# Adapters.net
KiCad netlist of a schematic drawn in Altium Designer
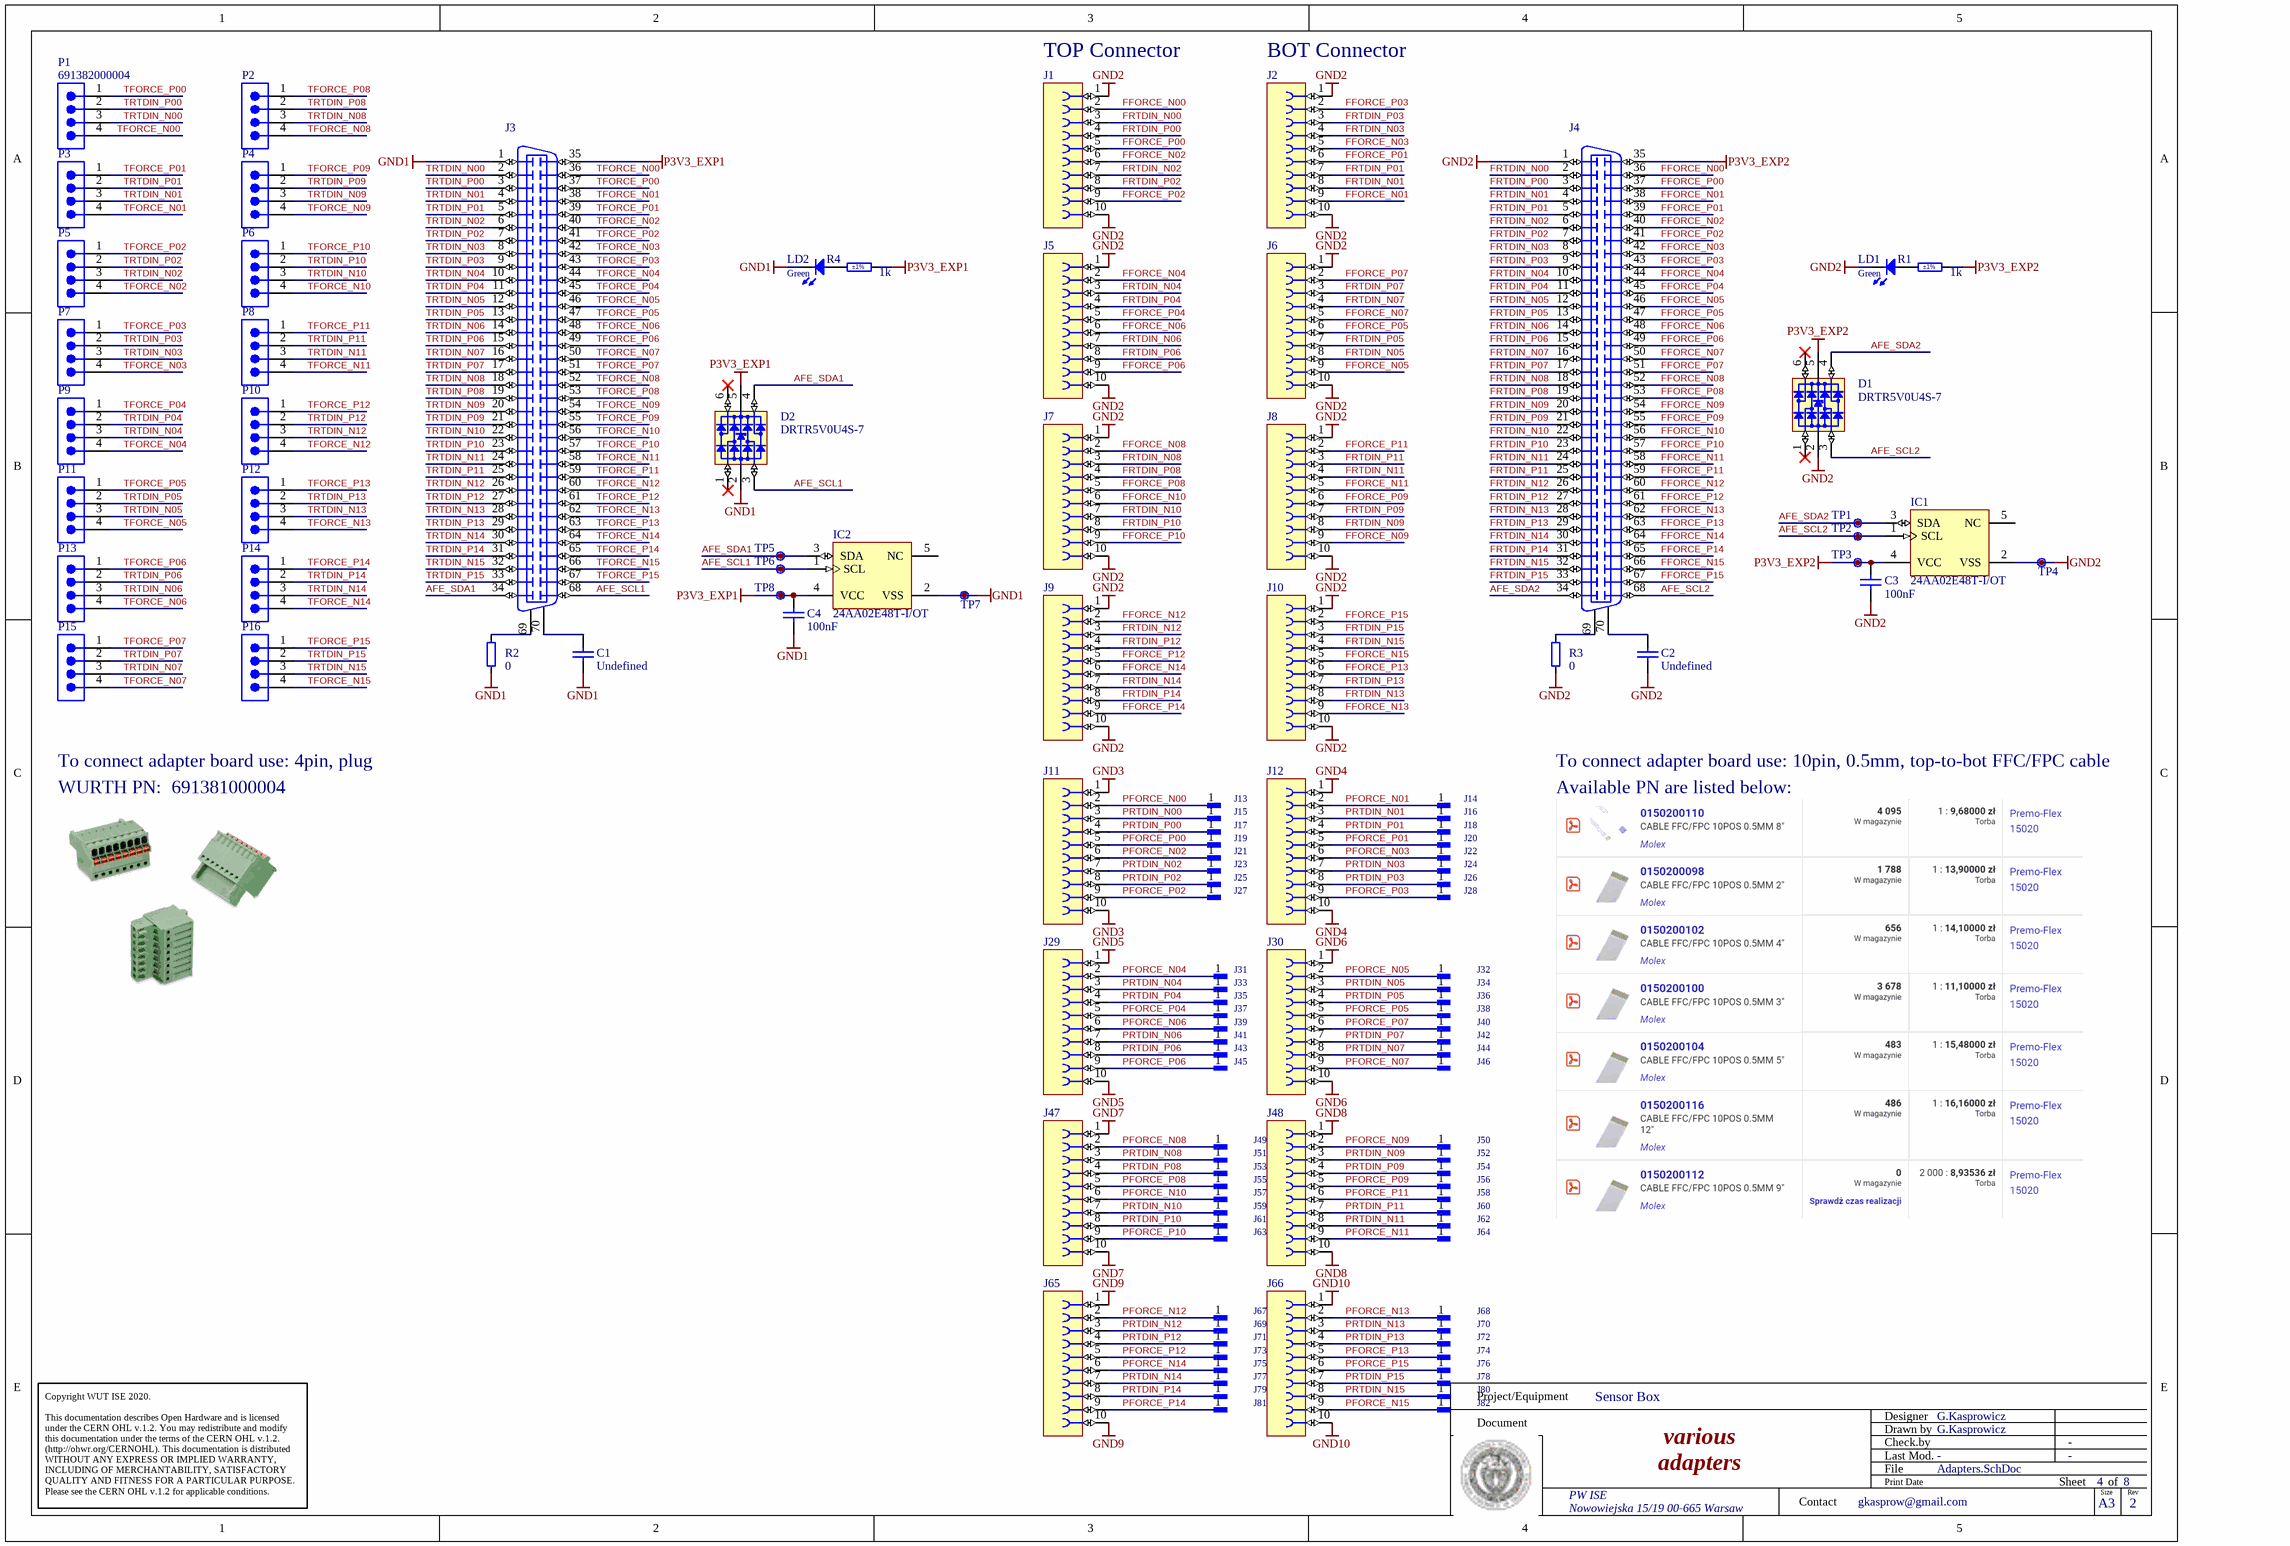
[diagram p0: Adapters.SchDoc]

(export (version "E")
  (design (tool "Eeschema 10.0.6"))
  (components
    (comp (ref "C1")
      (value "Undefined")
      (footprint "CAPC2012X135N")
      (description "Non-polarised capacitor")
      (fields (field (name "PART NUMBER") "CC0805_NO-VALUE") (field (name "AUTHOR") "CERN DEM JLC"))
      (libsource (lib "Capacitors") (part "Capacitor - non polarized"))
    )
    (comp (ref "C2")
      (value "Undefined")
      (footprint "CAPC2012X135N")
      (description "Non-polarised capacitor")
      (fields (field (name "PART NUMBER") "CC0805_NO-VALUE") (field (name "AUTHOR") "CERN DEM JLC"))
      (libsource (lib "Capacitors") (part "Capacitor - non polarized"))
    )
    (comp (ref "C3")
      (value "100nF")
      (footprint "CAPC1608X87N")
      (description "Non-polarised capacitor")
      (fields
        (field (name "PART NUMBER") "CC0603_100NF_50V_10%_X7R")
        (field (name "VOLTAGE") "50V")
        (field (name "AUTHOR") "CERN DEM JLC")
      )
      (libsource (lib "Capacitors") (part "Capacitor - non polarized"))
    )
    (comp (ref "C4")
      (value "100nF")
      (footprint "CAPC1608X87N")
      (description "Non-polarised capacitor")
      (fields
        (field (name "PART NUMBER") "CC0603_100NF_50V_10%_X7R")
        (field (name "VOLTAGE") "50V")
        (field (name "AUTHOR") "CERN DEM JLC")
      )
      (libsource (lib "Capacitors") (part "Capacitor - non polarized"))
    )
    (comp (ref "D1")
      (value "DRTR5V0U4S-7")
      (footprint "SOT65P210X110-6N")
      (description "Integrated Quad Ultra-Low Capacitance ESD Protection")
      (fields (field (name "MANUFACTURER") "DIODES") (field (name "AUTHOR") "GK"))
      (libsource (lib "Diodes") (part "D_TVS_DRTR5V0U4S-7"))
    )
    (comp (ref "D2")
      (value "DRTR5V0U4S-7")
      (footprint "SOT65P210X110-6N")
      (description "Integrated Quad Ultra-Low Capacitance ESD Protection")
      (fields (field (name "MANUFACTURER") "DIODES") (field (name "AUTHOR") "GK"))
      (libsource (lib "Diodes") (part "D_TVS_DRTR5V0U4S-7"))
    )
    (comp (ref "IC1")
      (value "24AA02E48T-I/OT")
      (footprint "SOT95P280X145-5N")
      (description "1.7V-5.5V, 2K I2C Serial EEPROM With EUI-48 Node Identity")
      (fields (field (name "MANUFACTURER") "MICROCHIP TECHNOLOGY") (field (name "AUTHOR") "CERN DEM MR"))
      (libsource (lib "ICs And Semiconductors") (part "24AA02E48T-I/OT"))
    )
    (comp (ref "IC2")
      (value "24AA02E48T-I/OT")
      (footprint "SOT95P280X145-5N")
      (description "1.7V-5.5V, 2K I2C Serial EEPROM With EUI-48 Node Identity")
      (fields (field (name "MANUFACTURER") "MICROCHIP TECHNOLOGY") (field (name "AUTHOR") "CERN DEM MR"))
      (libsource (lib "ICs And Semiconductors") (part "24AA02E48T-I/OT"))
    )
    (comp (ref "J1")
      (value "FFC/FPC")
      (footprint "MOLEX_52745-1097")
      (description "Connector 10 Female")
      (fields
        (field (name "PART NUMBER") "MOLEX_52745-1097")
        (field (name "MANUFACTURER") "MOLEX")
        (field (name "AUTHOR") "CERN DEM JLC")
      )
      (libsource (lib "Connectors") (part "Connector 10 Female"))
    )
    (comp (ref "J2")
      (value "FFC/FPC")
      (footprint "MOLEX_52745-1097")
      (description "Connector 10 Female")
      (fields
        (field (name "PART NUMBER") "MOLEX_52745-1097")
        (field (name "MANUFACTURER") "MOLEX")
        (field (name "AUTHOR") "CERN DEM JLC")
      )
      (libsource (lib "Connectors") (part "Connector 10 Female"))
    )
    (comp (ref "J3")
      (value "DNP")
      (footprint "MOLEX_71430-0013")
      (description "Very High Density Cable Interconnect (VHDCI ) 68 Female")
      (fields
        (field (name "PART NUMBER") "MOLEX_71430-0013")
        (field (name "MANUFACTURER") "MOLEX")
        (field (name "AUTHOR") "CERN DEM JLC")
      )
      (libsource (lib "DIOT_temperature_logger") (part "MOLEX_71430-0013"))
    )
    (comp (ref "J4")
      (value "DNP")
      (footprint "MOLEX_71430-0013")
      (description "Very High Density Cable Interconnect (VHDCI ) 68 Female")
      (fields
        (field (name "PART NUMBER") "MOLEX_71430-0013")
        (field (name "MANUFACTURER") "MOLEX")
        (field (name "AUTHOR") "CERN DEM JLC")
      )
      (libsource (lib "DIOT_temperature_logger") (part "MOLEX_71430-0013"))
    )
    (comp (ref "J5")
      (value "FFC/FPC")
      (footprint "MOLEX_52745-1097")
      (description "Connector 10 Female")
      (fields
        (field (name "PART NUMBER") "MOLEX_52745-1097")
        (field (name "MANUFACTURER") "MOLEX")
        (field (name "AUTHOR") "CERN DEM JLC")
      )
      (libsource (lib "Connectors") (part "Connector 10 Female"))
    )
    (comp (ref "J6")
      (value "FFC/FPC")
      (footprint "MOLEX_52745-1097")
      (description "Connector 10 Female")
      (fields
        (field (name "PART NUMBER") "MOLEX_52745-1097")
        (field (name "MANUFACTURER") "MOLEX")
        (field (name "AUTHOR") "CERN DEM JLC")
      )
      (libsource (lib "Connectors") (part "Connector 10 Female"))
    )
    (comp (ref "J7")
      (value "FFC/FPC")
      (footprint "MOLEX_52745-1097")
      (description "Connector 10 Female")
      (fields
        (field (name "PART NUMBER") "MOLEX_52745-1097")
        (field (name "MANUFACTURER") "MOLEX")
        (field (name "AUTHOR") "CERN DEM JLC")
      )
      (libsource (lib "Connectors") (part "Connector 10 Female"))
    )
    (comp (ref "J8")
      (value "FFC/FPC")
      (footprint "MOLEX_52745-1097")
      (description "Connector 10 Female")
      (fields
        (field (name "PART NUMBER") "MOLEX_52745-1097")
        (field (name "MANUFACTURER") "MOLEX")
        (field (name "AUTHOR") "CERN DEM JLC")
      )
      (libsource (lib "Connectors") (part "Connector 10 Female"))
    )
    (comp (ref "J9")
      (value "FFC/FPC")
      (footprint "MOLEX_52745-1097")
      (description "Connector 10 Female")
      (fields
        (field (name "PART NUMBER") "MOLEX_52745-1097")
        (field (name "MANUFACTURER") "MOLEX")
        (field (name "AUTHOR") "CERN DEM JLC")
      )
      (libsource (lib "Connectors") (part "Connector 10 Female"))
    )
    (comp (ref "J10")
      (value "FFC/FPC")
      (footprint "MOLEX_52745-1097")
      (description "Connector 10 Female")
      (fields
        (field (name "PART NUMBER") "MOLEX_52745-1097")
        (field (name "MANUFACTURER") "MOLEX")
        (field (name "AUTHOR") "CERN DEM JLC")
      )
      (libsource (lib "Connectors") (part "Connector 10 Female"))
    )
    (comp (ref "J11")
      (value "FFC/FPC")
      (footprint "MOLEX_52745-1097")
      (description "Connector 10 Female")
      (fields
        (field (name "PART NUMBER") "MOLEX_52745-1097")
        (field (name "MANUFACTURER") "MOLEX")
        (field (name "AUTHOR") "CERN DEM JLC")
      )
      (libsource (lib "Connectors") (part "Connector 10 Female"))
    )
    (comp (ref "J12")
      (value "FFC/FPC")
      (footprint "MOLEX_52745-1097")
      (description "Connector 10 Female")
      (fields
        (field (name "PART NUMBER") "MOLEX_52745-1097")
        (field (name "MANUFACTURER") "MOLEX")
        (field (name "AUTHOR") "CERN DEM JLC")
      )
      (libsource (lib "Connectors") (part "Connector 10 Female"))
    )
    (comp (ref "J13")
      (value "SMD Pad")
      (footprint "R350X200")
      (description "Pad")
      (fields (field (name "PART NUMBER") "SMD_PAD_3.5X2MM") (field (name "AUTHOR") "CERN DEM JLC"))
      (libsource (lib "Eletro-mechanical") (part "Single SMD Pad"))
    )
    (comp (ref "J14")
      (value "SMD Pad")
      (footprint "R350X200")
      (description "Pad")
      (fields (field (name "PART NUMBER") "SMD_PAD_3.5X2MM") (field (name "AUTHOR") "CERN DEM JLC"))
      (libsource (lib "Eletro-mechanical") (part "Single SMD Pad"))
    )
    (comp (ref "J15")
      (value "SMD Pad")
      (footprint "R350X200")
      (description "Pad")
      (fields (field (name "PART NUMBER") "SMD_PAD_3.5X2MM") (field (name "AUTHOR") "CERN DEM JLC"))
      (libsource (lib "Eletro-mechanical") (part "Single SMD Pad"))
    )
    (comp (ref "J16")
      (value "SMD Pad")
      (footprint "R350X200")
      (description "Pad")
      (fields (field (name "PART NUMBER") "SMD_PAD_3.5X2MM") (field (name "AUTHOR") "CERN DEM JLC"))
      (libsource (lib "Eletro-mechanical") (part "Single SMD Pad"))
    )
    (comp (ref "J17")
      (value "SMD Pad")
      (footprint "R350X200")
      (description "Pad")
      (fields (field (name "PART NUMBER") "SMD_PAD_3.5X2MM") (field (name "AUTHOR") "CERN DEM JLC"))
      (libsource (lib "Eletro-mechanical") (part "Single SMD Pad"))
    )
    (comp (ref "J18")
      (value "SMD Pad")
      (footprint "R350X200")
      (description "Pad")
      (fields (field (name "PART NUMBER") "SMD_PAD_3.5X2MM") (field (name "AUTHOR") "CERN DEM JLC"))
      (libsource (lib "Eletro-mechanical") (part "Single SMD Pad"))
    )
    (comp (ref "J19")
      (value "SMD Pad")
      (footprint "R350X200")
      (description "Pad")
      (fields (field (name "PART NUMBER") "SMD_PAD_3.5X2MM") (field (name "AUTHOR") "CERN DEM JLC"))
      (libsource (lib "Eletro-mechanical") (part "Single SMD Pad"))
    )
    (comp (ref "J20")
      (value "SMD Pad")
      (footprint "R350X200")
      (description "Pad")
      (fields (field (name "PART NUMBER") "SMD_PAD_3.5X2MM") (field (name "AUTHOR") "CERN DEM JLC"))
      (libsource (lib "Eletro-mechanical") (part "Single SMD Pad"))
    )
    (comp (ref "J21")
      (value "SMD Pad")
      (footprint "R350X200")
      (description "Pad")
      (fields (field (name "PART NUMBER") "SMD_PAD_3.5X2MM") (field (name "AUTHOR") "CERN DEM JLC"))
      (libsource (lib "Eletro-mechanical") (part "Single SMD Pad"))
    )
    (comp (ref "J22")
      (value "SMD Pad")
      (footprint "R350X200")
      (description "Pad")
      (fields (field (name "PART NUMBER") "SMD_PAD_3.5X2MM") (field (name "AUTHOR") "CERN DEM JLC"))
      (libsource (lib "Eletro-mechanical") (part "Single SMD Pad"))
    )
    (comp (ref "J23")
      (value "SMD Pad")
      (footprint "R350X200")
      (description "Pad")
      (fields (field (name "PART NUMBER") "SMD_PAD_3.5X2MM") (field (name "AUTHOR") "CERN DEM JLC"))
      (libsource (lib "Eletro-mechanical") (part "Single SMD Pad"))
    )
    (comp (ref "J24")
      (value "SMD Pad")
      (footprint "R350X200")
      (description "Pad")
      (fields (field (name "PART NUMBER") "SMD_PAD_3.5X2MM") (field (name "AUTHOR") "CERN DEM JLC"))
      (libsource (lib "Eletro-mechanical") (part "Single SMD Pad"))
    )
    (comp (ref "J25")
      (value "SMD Pad")
      (footprint "R350X200")
      (description "Pad")
      (fields (field (name "PART NUMBER") "SMD_PAD_3.5X2MM") (field (name "AUTHOR") "CERN DEM JLC"))
      (libsource (lib "Eletro-mechanical") (part "Single SMD Pad"))
    )
    (comp (ref "J26")
      (value "SMD Pad")
      (footprint "R350X200")
      (description "Pad")
      (fields (field (name "PART NUMBER") "SMD_PAD_3.5X2MM") (field (name "AUTHOR") "CERN DEM JLC"))
      (libsource (lib "Eletro-mechanical") (part "Single SMD Pad"))
    )
    (comp (ref "J27")
      (value "SMD Pad")
      (footprint "R350X200")
      (description "Pad")
      (fields (field (name "PART NUMBER") "SMD_PAD_3.5X2MM") (field (name "AUTHOR") "CERN DEM JLC"))
      (libsource (lib "Eletro-mechanical") (part "Single SMD Pad"))
    )
    (comp (ref "J28")
      (value "SMD Pad")
      (footprint "R350X200")
      (description "Pad")
      (fields (field (name "PART NUMBER") "SMD_PAD_3.5X2MM") (field (name "AUTHOR") "CERN DEM JLC"))
      (libsource (lib "Eletro-mechanical") (part "Single SMD Pad"))
    )
    (comp (ref "J29")
      (value "FFC/FPC")
      (footprint "MOLEX_52745-1097")
      (description "Connector 10 Female")
      (fields
        (field (name "PART NUMBER") "MOLEX_52745-1097")
        (field (name "MANUFACTURER") "MOLEX")
        (field (name "AUTHOR") "CERN DEM JLC")
      )
      (libsource (lib "Connectors") (part "Connector 10 Female"))
    )
    (comp (ref "J30")
      (value "FFC/FPC")
      (footprint "MOLEX_52745-1097")
      (description "Connector 10 Female")
      (fields
        (field (name "PART NUMBER") "MOLEX_52745-1097")
        (field (name "MANUFACTURER") "MOLEX")
        (field (name "AUTHOR") "CERN DEM JLC")
      )
      (libsource (lib "Connectors") (part "Connector 10 Female"))
    )
    (comp (ref "J31")
      (value "SMD Pad")
      (footprint "R350X200")
      (description "Pad")
      (fields (field (name "PART NUMBER") "SMD_PAD_3.5X2MM") (field (name "AUTHOR") "CERN DEM JLC"))
      (libsource (lib "Eletro-mechanical") (part "Single SMD Pad"))
    )
    (comp (ref "J32")
      (value "SMD Pad")
      (footprint "R350X200")
      (description "Pad")
      (fields (field (name "PART NUMBER") "SMD_PAD_3.5X2MM") (field (name "AUTHOR") "CERN DEM JLC"))
      (libsource (lib "Eletro-mechanical") (part "Single SMD Pad"))
    )
    (comp (ref "J33")
      (value "SMD Pad")
      (footprint "R350X200")
      (description "Pad")
      (fields (field (name "PART NUMBER") "SMD_PAD_3.5X2MM") (field (name "AUTHOR") "CERN DEM JLC"))
      (libsource (lib "Eletro-mechanical") (part "Single SMD Pad"))
    )
    (comp (ref "J34")
      (value "SMD Pad")
      (footprint "R350X200")
      (description "Pad")
      (fields (field (name "PART NUMBER") "SMD_PAD_3.5X2MM") (field (name "AUTHOR") "CERN DEM JLC"))
      (libsource (lib "Eletro-mechanical") (part "Single SMD Pad"))
    )
    (comp (ref "J35")
      (value "SMD Pad")
      (footprint "R350X200")
      (description "Pad")
      (fields (field (name "PART NUMBER") "SMD_PAD_3.5X2MM") (field (name "AUTHOR") "CERN DEM JLC"))
      (libsource (lib "Eletro-mechanical") (part "Single SMD Pad"))
    )
    (comp (ref "J36")
      (value "SMD Pad")
      (footprint "R350X200")
      (description "Pad")
      (fields (field (name "PART NUMBER") "SMD_PAD_3.5X2MM") (field (name "AUTHOR") "CERN DEM JLC"))
      (libsource (lib "Eletro-mechanical") (part "Single SMD Pad"))
    )
    (comp (ref "J37")
      (value "SMD Pad")
      (footprint "R350X200")
      (description "Pad")
      (fields (field (name "PART NUMBER") "SMD_PAD_3.5X2MM") (field (name "AUTHOR") "CERN DEM JLC"))
      (libsource (lib "Eletro-mechanical") (part "Single SMD Pad"))
    )
    (comp (ref "J38")
      (value "SMD Pad")
      (footprint "R350X200")
      (description "Pad")
      (fields (field (name "PART NUMBER") "SMD_PAD_3.5X2MM") (field (name "AUTHOR") "CERN DEM JLC"))
      (libsource (lib "Eletro-mechanical") (part "Single SMD Pad"))
    )
    (comp (ref "J39")
      (value "SMD Pad")
      (footprint "R350X200")
      (description "Pad")
      (fields (field (name "PART NUMBER") "SMD_PAD_3.5X2MM") (field (name "AUTHOR") "CERN DEM JLC"))
      (libsource (lib "Eletro-mechanical") (part "Single SMD Pad"))
    )
    (comp (ref "J40")
      (value "SMD Pad")
      (footprint "R350X200")
      (description "Pad")
      (fields (field (name "PART NUMBER") "SMD_PAD_3.5X2MM") (field (name "AUTHOR") "CERN DEM JLC"))
      (libsource (lib "Eletro-mechanical") (part "Single SMD Pad"))
    )
    (comp (ref "J41")
      (value "SMD Pad")
      (footprint "R350X200")
      (description "Pad")
      (fields (field (name "PART NUMBER") "SMD_PAD_3.5X2MM") (field (name "AUTHOR") "CERN DEM JLC"))
      (libsource (lib "Eletro-mechanical") (part "Single SMD Pad"))
    )
    (comp (ref "J42")
      (value "SMD Pad")
      (footprint "R350X200")
      (description "Pad")
      (fields (field (name "PART NUMBER") "SMD_PAD_3.5X2MM") (field (name "AUTHOR") "CERN DEM JLC"))
      (libsource (lib "Eletro-mechanical") (part "Single SMD Pad"))
    )
    (comp (ref "J43")
      (value "SMD Pad")
      (footprint "R350X200")
      (description "Pad")
      (fields (field (name "PART NUMBER") "SMD_PAD_3.5X2MM") (field (name "AUTHOR") "CERN DEM JLC"))
      (libsource (lib "Eletro-mechanical") (part "Single SMD Pad"))
    )
    (comp (ref "J44")
      (value "SMD Pad")
      (footprint "R350X200")
      (description "Pad")
      (fields (field (name "PART NUMBER") "SMD_PAD_3.5X2MM") (field (name "AUTHOR") "CERN DEM JLC"))
      (libsource (lib "Eletro-mechanical") (part "Single SMD Pad"))
    )
    (comp (ref "J45")
      (value "SMD Pad")
      (footprint "R350X200")
      (description "Pad")
      (fields (field (name "PART NUMBER") "SMD_PAD_3.5X2MM") (field (name "AUTHOR") "CERN DEM JLC"))
      (libsource (lib "Eletro-mechanical") (part "Single SMD Pad"))
    )
    (comp (ref "J46")
      (value "SMD Pad")
      (footprint "R350X200")
      (description "Pad")
      (fields (field (name "PART NUMBER") "SMD_PAD_3.5X2MM") (field (name "AUTHOR") "CERN DEM JLC"))
      (libsource (lib "Eletro-mechanical") (part "Single SMD Pad"))
    )
    (comp (ref "J47")
      (value "FFC/FPC")
      (footprint "MOLEX_52745-1097")
      (description "Connector 10 Female")
      (fields
        (field (name "PART NUMBER") "MOLEX_52745-1097")
        (field (name "MANUFACTURER") "MOLEX")
        (field (name "AUTHOR") "CERN DEM JLC")
      )
      (libsource (lib "Connectors") (part "Connector 10 Female"))
    )
    (comp (ref "J48")
      (value "FFC/FPC")
      (footprint "MOLEX_52745-1097")
      (description "Connector 10 Female")
      (fields
        (field (name "PART NUMBER") "MOLEX_52745-1097")
        (field (name "MANUFACTURER") "MOLEX")
        (field (name "AUTHOR") "CERN DEM JLC")
      )
      (libsource (lib "Connectors") (part "Connector 10 Female"))
    )
    (comp (ref "J49")
      (value "SMD Pad")
      (footprint "R350X200")
      (description "Pad")
      (fields (field (name "PART NUMBER") "SMD_PAD_3.5X2MM") (field (name "AUTHOR") "CERN DEM JLC"))
      (libsource (lib "Eletro-mechanical") (part "Single SMD Pad"))
    )
    (comp (ref "J50")
      (value "SMD Pad")
      (footprint "R350X200")
      (description "Pad")
      (fields (field (name "PART NUMBER") "SMD_PAD_3.5X2MM") (field (name "AUTHOR") "CERN DEM JLC"))
      (libsource (lib "Eletro-mechanical") (part "Single SMD Pad"))
    )
    (comp (ref "J51")
      (value "SMD Pad")
      (footprint "R350X200")
      (description "Pad")
      (fields (field (name "PART NUMBER") "SMD_PAD_3.5X2MM") (field (name "AUTHOR") "CERN DEM JLC"))
      (libsource (lib "Eletro-mechanical") (part "Single SMD Pad"))
    )
    (comp (ref "J52")
      (value "SMD Pad")
      (footprint "R350X200")
      (description "Pad")
      (fields (field (name "PART NUMBER") "SMD_PAD_3.5X2MM") (field (name "AUTHOR") "CERN DEM JLC"))
      (libsource (lib "Eletro-mechanical") (part "Single SMD Pad"))
    )
    (comp (ref "J53")
      (value "SMD Pad")
      (footprint "R350X200")
      (description "Pad")
      (fields (field (name "PART NUMBER") "SMD_PAD_3.5X2MM") (field (name "AUTHOR") "CERN DEM JLC"))
      (libsource (lib "Eletro-mechanical") (part "Single SMD Pad"))
    )
    (comp (ref "J54")
      (value "SMD Pad")
      (footprint "R350X200")
      (description "Pad")
      (fields (field (name "PART NUMBER") "SMD_PAD_3.5X2MM") (field (name "AUTHOR") "CERN DEM JLC"))
      (libsource (lib "Eletro-mechanical") (part "Single SMD Pad"))
    )
    (comp (ref "J55")
      (value "SMD Pad")
      (footprint "R350X200")
      (description "Pad")
      (fields (field (name "PART NUMBER") "SMD_PAD_3.5X2MM") (field (name "AUTHOR") "CERN DEM JLC"))
      (libsource (lib "Eletro-mechanical") (part "Single SMD Pad"))
    )
    (comp (ref "J56")
      (value "SMD Pad")
      (footprint "R350X200")
      (description "Pad")
      (fields (field (name "PART NUMBER") "SMD_PAD_3.5X2MM") (field (name "AUTHOR") "CERN DEM JLC"))
      (libsource (lib "Eletro-mechanical") (part "Single SMD Pad"))
    )
    (comp (ref "J57")
      (value "SMD Pad")
      (footprint "R350X200")
      (description "Pad")
      (fields (field (name "PART NUMBER") "SMD_PAD_3.5X2MM") (field (name "AUTHOR") "CERN DEM JLC"))
      (libsource (lib "Eletro-mechanical") (part "Single SMD Pad"))
    )
    (comp (ref "J58")
      (value "SMD Pad")
      (footprint "R350X200")
      (description "Pad")
      (fields (field (name "PART NUMBER") "SMD_PAD_3.5X2MM") (field (name "AUTHOR") "CERN DEM JLC"))
      (libsource (lib "Eletro-mechanical") (part "Single SMD Pad"))
    )
    (comp (ref "J59")
      (value "SMD Pad")
      (footprint "R350X200")
      (description "Pad")
      (fields (field (name "PART NUMBER") "SMD_PAD_3.5X2MM") (field (name "AUTHOR") "CERN DEM JLC"))
      (libsource (lib "Eletro-mechanical") (part "Single SMD Pad"))
    )
    (comp (ref "J60")
      (value "SMD Pad")
      (footprint "R350X200")
      (description "Pad")
      (fields (field (name "PART NUMBER") "SMD_PAD_3.5X2MM") (field (name "AUTHOR") "CERN DEM JLC"))
      (libsource (lib "Eletro-mechanical") (part "Single SMD Pad"))
    )
    (comp (ref "J61")
      (value "SMD Pad")
      (footprint "R350X200")
      (description "Pad")
      (fields (field (name "PART NUMBER") "SMD_PAD_3.5X2MM") (field (name "AUTHOR") "CERN DEM JLC"))
      (libsource (lib "Eletro-mechanical") (part "Single SMD Pad"))
    )
    (comp (ref "J62")
      (value "SMD Pad")
      (footprint "R350X200")
      (description "Pad")
      (fields (field (name "PART NUMBER") "SMD_PAD_3.5X2MM") (field (name "AUTHOR") "CERN DEM JLC"))
      (libsource (lib "Eletro-mechanical") (part "Single SMD Pad"))
    )
    (comp (ref "J63")
      (value "SMD Pad")
      (footprint "R350X200")
      (description "Pad")
      (fields (field (name "PART NUMBER") "SMD_PAD_3.5X2MM") (field (name "AUTHOR") "CERN DEM JLC"))
      (libsource (lib "Eletro-mechanical") (part "Single SMD Pad"))
    )
    (comp (ref "J64")
      (value "SMD Pad")
      (footprint "R350X200")
      (description "Pad")
      (fields (field (name "PART NUMBER") "SMD_PAD_3.5X2MM") (field (name "AUTHOR") "CERN DEM JLC"))
      (libsource (lib "Eletro-mechanical") (part "Single SMD Pad"))
    )
    (comp (ref "J65")
      (value "FFC/FPC")
      (footprint "MOLEX_52745-1097")
      (description "Connector 10 Female")
      (fields
        (field (name "PART NUMBER") "MOLEX_52745-1097")
        (field (name "MANUFACTURER") "MOLEX")
        (field (name "AUTHOR") "CERN DEM JLC")
      )
      (libsource (lib "Connectors") (part "Connector 10 Female"))
    )
    (comp (ref "J66")
      (value "FFC/FPC")
      (footprint "MOLEX_52745-1097")
      (description "Connector 10 Female")
      (fields
        (field (name "PART NUMBER") "MOLEX_52745-1097")
        (field (name "MANUFACTURER") "MOLEX")
        (field (name "AUTHOR") "CERN DEM JLC")
      )
      (libsource (lib "Connectors") (part "Connector 10 Female"))
    )
    (comp (ref "J67")
      (value "SMD Pad")
      (footprint "R350X200")
      (description "Pad")
      (fields (field (name "PART NUMBER") "SMD_PAD_3.5X2MM") (field (name "AUTHOR") "CERN DEM JLC"))
      (libsource (lib "Eletro-mechanical") (part "Single SMD Pad"))
    )
    (comp (ref "J68")
      (value "SMD Pad")
      (footprint "R350X200")
      (description "Pad")
      (fields (field (name "PART NUMBER") "SMD_PAD_3.5X2MM") (field (name "AUTHOR") "CERN DEM JLC"))
      (libsource (lib "Eletro-mechanical") (part "Single SMD Pad"))
    )
    (comp (ref "J69")
      (value "SMD Pad")
      (footprint "R350X200")
      (description "Pad")
      (fields (field (name "PART NUMBER") "SMD_PAD_3.5X2MM") (field (name "AUTHOR") "CERN DEM JLC"))
      (libsource (lib "Eletro-mechanical") (part "Single SMD Pad"))
    )
    (comp (ref "J70")
      (value "SMD Pad")
      (footprint "R350X200")
      (description "Pad")
      (fields (field (name "PART NUMBER") "SMD_PAD_3.5X2MM") (field (name "AUTHOR") "CERN DEM JLC"))
      (libsource (lib "Eletro-mechanical") (part "Single SMD Pad"))
    )
    (comp (ref "J71")
      (value "SMD Pad")
      (footprint "R350X200")
      (description "Pad")
      (fields (field (name "PART NUMBER") "SMD_PAD_3.5X2MM") (field (name "AUTHOR") "CERN DEM JLC"))
      (libsource (lib "Eletro-mechanical") (part "Single SMD Pad"))
    )
    (comp (ref "J72")
      (value "SMD Pad")
      (footprint "R350X200")
      (description "Pad")
      (fields (field (name "PART NUMBER") "SMD_PAD_3.5X2MM") (field (name "AUTHOR") "CERN DEM JLC"))
      (libsource (lib "Eletro-mechanical") (part "Single SMD Pad"))
    )
    (comp (ref "J73")
      (value "SMD Pad")
      (footprint "R350X200")
      (description "Pad")
      (fields (field (name "PART NUMBER") "SMD_PAD_3.5X2MM") (field (name "AUTHOR") "CERN DEM JLC"))
      (libsource (lib "Eletro-mechanical") (part "Single SMD Pad"))
    )
    (comp (ref "J74")
      (value "SMD Pad")
      (footprint "R350X200")
      (description "Pad")
      (fields (field (name "PART NUMBER") "SMD_PAD_3.5X2MM") (field (name "AUTHOR") "CERN DEM JLC"))
      (libsource (lib "Eletro-mechanical") (part "Single SMD Pad"))
    )
    (comp (ref "J75")
      (value "SMD Pad")
      (footprint "R350X200")
      (description "Pad")
      (fields (field (name "PART NUMBER") "SMD_PAD_3.5X2MM") (field (name "AUTHOR") "CERN DEM JLC"))
      (libsource (lib "Eletro-mechanical") (part "Single SMD Pad"))
    )
    (comp (ref "J76")
      (value "SMD Pad")
      (footprint "R350X200")
      (description "Pad")
      (fields (field (name "PART NUMBER") "SMD_PAD_3.5X2MM") (field (name "AUTHOR") "CERN DEM JLC"))
      (libsource (lib "Eletro-mechanical") (part "Single SMD Pad"))
    )
    (comp (ref "J77")
      (value "SMD Pad")
      (footprint "R350X200")
      (description "Pad")
      (fields (field (name "PART NUMBER") "SMD_PAD_3.5X2MM") (field (name "AUTHOR") "CERN DEM JLC"))
      (libsource (lib "Eletro-mechanical") (part "Single SMD Pad"))
    )
    (comp (ref "J78")
      (value "SMD Pad")
      (footprint "R350X200")
      (description "Pad")
      (fields (field (name "PART NUMBER") "SMD_PAD_3.5X2MM") (field (name "AUTHOR") "CERN DEM JLC"))
      (libsource (lib "Eletro-mechanical") (part "Single SMD Pad"))
    )
    (comp (ref "J79")
      (value "SMD Pad")
      (footprint "R350X200")
      (description "Pad")
      (fields (field (name "PART NUMBER") "SMD_PAD_3.5X2MM") (field (name "AUTHOR") "CERN DEM JLC"))
      (libsource (lib "Eletro-mechanical") (part "Single SMD Pad"))
    )
    (comp (ref "J80")
      (value "SMD Pad")
      (footprint "R350X200")
      (description "Pad")
      (fields (field (name "PART NUMBER") "SMD_PAD_3.5X2MM") (field (name "AUTHOR") "CERN DEM JLC"))
      (libsource (lib "Eletro-mechanical") (part "Single SMD Pad"))
    )
    (comp (ref "J81")
      (value "SMD Pad")
      (footprint "R350X200")
      (description "Pad")
      (fields (field (name "PART NUMBER") "SMD_PAD_3.5X2MM") (field (name "AUTHOR") "CERN DEM JLC"))
      (libsource (lib "Eletro-mechanical") (part "Single SMD Pad"))
    )
    (comp (ref "J82")
      (value "SMD Pad")
      (footprint "R350X200")
      (description "Pad")
      (fields (field (name "PART NUMBER") "SMD_PAD_3.5X2MM") (field (name "AUTHOR") "CERN DEM JLC"))
      (libsource (lib "Eletro-mechanical") (part "Single SMD Pad"))
    )
    (comp (ref "LD1")
      (value "Green")
      (footprint "LED_KINGBRIGHT_KPH-1608CGCK")
      (description "LED Green 1C 2A")
      (fields
        (field (name "PART NUMBER") "LED_KINGBRIGHT_KPH-1608CGCK")
        (field (name "MANUFACTURER") "KINGBRIGHT")
        (field (name "AUTHOR") "CERN DEM JLC")
      )
      (libsource (lib "ICs And Semiconductors") (part "LED Green 1C 2A"))
    )
    (comp (ref "LD2")
      (value "Green")
      (footprint "LED_KINGBRIGHT_KPH-1608CGCK")
      (description "LED Green 1C 2A")
      (fields
        (field (name "PART NUMBER") "LED_KINGBRIGHT_KPH-1608CGCK")
        (field (name "MANUFACTURER") "KINGBRIGHT")
        (field (name "AUTHOR") "CERN DEM JLC")
      )
      (libsource (lib "ICs And Semiconductors") (part "LED Green 1C 2A"))
    )
    (comp (ref "P1")
      (value "691382000004")
      (footprint "691382000004")
      (description "WR-TBL Series 382 Vertical PCB Header, THT, pitch 2.5mm, 4p")
      (fields
        (field (name "MANUFACTURER PART NUMBER") "691382000004")
        (field (name "MANUFACTURER") "Wurth Elektronik")
      )
      (libsource (lib "Altium_WR-TBL (rev23f)") (part "691382000004"))
    )
    (comp (ref "P2")
      (value "691382000004")
      (footprint "691382000004")
      (description "WR-TBL Series 382 Vertical PCB Header, THT, pitch 2.5mm, 4p")
      (fields (field (name "MANUFACTURER") "Wurth Elektronik"))
      (libsource (lib "Altium_WR-TBL (rev23f)") (part "691382000004"))
    )
    (comp (ref "P3")
      (value "691382000004")
      (footprint "691382000004")
      (description "WR-TBL Series 382 Vertical PCB Header, THT, pitch 2.5mm, 4p")
      (fields (field (name "MANUFACTURER") "Wurth Elektronik"))
      (libsource (lib "Altium_WR-TBL (rev23f)") (part "691382000004"))
    )
    (comp (ref "P4")
      (value "691382000004")
      (footprint "691382000004")
      (description "WR-TBL Series 382 Vertical PCB Header, THT, pitch 2.5mm, 4p")
      (fields (field (name "MANUFACTURER") "Wurth Elektronik"))
      (libsource (lib "Altium_WR-TBL (rev23f)") (part "691382000004"))
    )
    (comp (ref "P5")
      (value "691382000004")
      (footprint "691382000004")
      (description "WR-TBL Series 382 Vertical PCB Header, THT, pitch 2.5mm, 4p")
      (fields (field (name "MANUFACTURER") "Wurth Elektronik"))
      (libsource (lib "Altium_WR-TBL (rev23f)") (part "691382000004"))
    )
    (comp (ref "P6")
      (value "691382000004")
      (footprint "691382000004")
      (description "WR-TBL Series 382 Vertical PCB Header, THT, pitch 2.5mm, 4p")
      (fields (field (name "MANUFACTURER") "Wurth Elektronik"))
      (libsource (lib "Altium_WR-TBL (rev23f)") (part "691382000004"))
    )
    (comp (ref "P7")
      (value "691382000004")
      (footprint "691382000004")
      (description "WR-TBL Series 382 Vertical PCB Header, THT, pitch 2.5mm, 4p")
      (fields (field (name "MANUFACTURER") "Wurth Elektronik"))
      (libsource (lib "Altium_WR-TBL (rev23f)") (part "691382000004"))
    )
    (comp (ref "P8")
      (value "691382000004")
      (footprint "691382000004")
      (description "WR-TBL Series 382 Vertical PCB Header, THT, pitch 2.5mm, 4p")
      (fields (field (name "MANUFACTURER") "Wurth Elektronik"))
      (libsource (lib "Altium_WR-TBL (rev23f)") (part "691382000004"))
    )
    (comp (ref "P9")
      (value "691382000004")
      (footprint "691382000004")
      (description "WR-TBL Series 382 Vertical PCB Header, THT, pitch 2.5mm, 4p")
      (fields (field (name "MANUFACTURER") "Wurth Elektronik"))
      (libsource (lib "Altium_WR-TBL (rev23f)") (part "691382000004"))
    )
    (comp (ref "P10")
      (value "691382000004")
      (footprint "691382000004")
      (description "WR-TBL Series 382 Vertical PCB Header, THT, pitch 2.5mm, 4p")
      (fields (field (name "MANUFACTURER") "Wurth Elektronik"))
      (libsource (lib "Altium_WR-TBL (rev23f)") (part "691382000004"))
    )
    (comp (ref "P11")
      (value "691382000004")
      (footprint "691382000004")
      (description "WR-TBL Series 382 Vertical PCB Header, THT, pitch 2.5mm, 4p")
      (fields (field (name "MANUFACTURER") "Wurth Elektronik"))
      (libsource (lib "Altium_WR-TBL (rev23f)") (part "691382000004"))
    )
    (comp (ref "P12")
      (value "691382000004")
      (footprint "691382000004")
      (description "WR-TBL Series 382 Vertical PCB Header, THT, pitch 2.5mm, 4p")
      (fields (field (name "MANUFACTURER") "Wurth Elektronik"))
      (libsource (lib "Altium_WR-TBL (rev23f)") (part "691382000004"))
    )
    (comp (ref "P13")
      (value "691382000004")
      (footprint "691382000004")
      (description "WR-TBL Series 382 Vertical PCB Header, THT, pitch 2.5mm, 4p")
      (fields (field (name "MANUFACTURER") "Wurth Elektronik"))
      (libsource (lib "Altium_WR-TBL (rev23f)") (part "691382000004"))
    )
    (comp (ref "P14")
      (value "691382000004")
      (footprint "691382000004")
      (description "WR-TBL Series 382 Vertical PCB Header, THT, pitch 2.5mm, 4p")
      (fields (field (name "MANUFACTURER") "Wurth Elektronik"))
      (libsource (lib "Altium_WR-TBL (rev23f)") (part "691382000004"))
    )
    (comp (ref "P15")
      (value "691382000004")
      (footprint "691382000004")
      (description "WR-TBL Series 382 Vertical PCB Header, THT, pitch 2.5mm, 4p")
      (fields (field (name "MANUFACTURER") "Wurth Elektronik"))
      (libsource (lib "Altium_WR-TBL (rev23f)") (part "691382000004"))
    )
    (comp (ref "P16")
      (value "691382000004")
      (footprint "691382000004")
      (description "WR-TBL Series 382 Vertical PCB Header, THT, pitch 2.5mm, 4p")
      (fields (field (name "MANUFACTURER") "Wurth Elektronik"))
      (libsource (lib "Altium_WR-TBL (rev23f)") (part "691382000004"))
    )
    (comp (ref "R1")
      (value "1k")
      (footprint "RESC1608X55N")
      (description "Resistor - 1%")
      (fields
        (field (name "TOLERANCE") "±1%")
        (field (name "PART NUMBER") "R0603_1K_1%_0.1W_100PPM")
        (field (name "POWER") "0.1W")
        (field (name "AUTHOR") "CERN DEM JLC")
      )
      (libsource (lib "Resistors") (part "Resistor - 1%"))
    )
    (comp (ref "R2")
      (value "0")
      (footprint "RESC1608X55N")
      (description "Resistor")
      (fields
        (field (name "PART NUMBER") "R0603_0R_JUMPER")
        (field (name "MANUFACTURER") "GENERIC")
        (field (name "AUTHOR") "CERN DEM JLC")
      )
      (libsource (lib "Resistors") (part "Resistor"))
    )
    (comp (ref "R3")
      (value "0")
      (footprint "RESC1608X55N")
      (description "Resistor")
      (fields
        (field (name "PART NUMBER") "R0603_0R_JUMPER")
        (field (name "MANUFACTURER") "GENERIC")
        (field (name "AUTHOR") "CERN DEM JLC")
      )
      (libsource (lib "Resistors") (part "Resistor"))
    )
    (comp (ref "R4")
      (value "1k")
      (footprint "RESC1608X55N")
      (description "Resistor - 1%")
      (fields
        (field (name "TOLERANCE") "±1%")
        (field (name "PART NUMBER") "R0603_1K_1%_0.1W_100PPM")
        (field (name "POWER") "0.1W")
        (field (name "AUTHOR") "CERN DEM JLC")
      )
      (libsource (lib "Resistors") (part "Resistor - 1%"))
    )
    (comp (ref "TP1")
      (value "Test Point")
      (footprint "TPS127")
      (fields (field (name "PART NUMBER") "SMD_PAD_1.27X1.27MM") (field (name "AUTHOR") "CERN DEM JLC"))
      (libsource (lib "Eletro-mechanical") (part "Test Point"))
    )
    (comp (ref "TP2")
      (value "Test Point")
      (footprint "TPS127")
      (fields (field (name "PART NUMBER") "SMD_PAD_1.27X1.27MM") (field (name "AUTHOR") "CERN DEM JLC"))
      (libsource (lib "Eletro-mechanical") (part "Test Point"))
    )
    (comp (ref "TP3")
      (value "Test Point")
      (footprint "TPS127")
      (fields (field (name "PART NUMBER") "SMD_PAD_1.27X1.27MM") (field (name "AUTHOR") "CERN DEM JLC"))
      (libsource (lib "Eletro-mechanical") (part "Test Point"))
    )
    (comp (ref "TP4")
      (value "Test Point")
      (footprint "TPS127")
      (fields (field (name "PART NUMBER") "SMD_PAD_1.27X1.27MM") (field (name "AUTHOR") "CERN DEM JLC"))
      (libsource (lib "Eletro-mechanical") (part "Test Point"))
    )
    (comp (ref "TP5")
      (value "Test Point")
      (footprint "TPS127")
      (fields (field (name "PART NUMBER") "SMD_PAD_1.27X1.27MM") (field (name "AUTHOR") "CERN DEM JLC"))
      (libsource (lib "Eletro-mechanical") (part "Test Point"))
    )
    (comp (ref "TP6")
      (value "Test Point")
      (footprint "TPS127")
      (fields (field (name "PART NUMBER") "SMD_PAD_1.27X1.27MM") (field (name "AUTHOR") "CERN DEM JLC"))
      (libsource (lib "Eletro-mechanical") (part "Test Point"))
    )
    (comp (ref "TP7")
      (value "Test Point")
      (footprint "TPS127")
      (fields (field (name "PART NUMBER") "SMD_PAD_1.27X1.27MM") (field (name "AUTHOR") "CERN DEM JLC"))
      (libsource (lib "Eletro-mechanical") (part "Test Point"))
    )
    (comp (ref "TP8")
      (value "Test Point")
      (footprint "TPS127")
      (fields (field (name "PART NUMBER") "SMD_PAD_1.27X1.27MM") (field (name "AUTHOR") "CERN DEM JLC"))
      (libsource (lib "Eletro-mechanical") (part "Test Point"))
    )
  )
  (nets
    (net (code "1") (name "/AFE_SCL1") (class "Default")
      (node (ref "D2") (pin "3") (pinfunction "I/O2_3") (pintype "bidirectional"))
      (node (ref "IC2") (pin "1") (pinfunction "SCL_1") (pintype "input"))
      (node (ref "J3") (pin "68") (pinfunction "68_68") (pintype "bidirectional"))
      (node (ref "TP6") (pin "1") (pinfunction "1_1") (pintype "bidirectional"))
    )
    (net (code "2") (name "/AFE_SCL2") (class "Default")
      (node (ref "D1") (pin "3") (pinfunction "I/O2_3") (pintype "bidirectional"))
      (node (ref "IC1") (pin "1") (pinfunction "SCL_1") (pintype "input"))
      (node (ref "J4") (pin "68") (pinfunction "68_68") (pintype "bidirectional"))
      (node (ref "TP2") (pin "1") (pinfunction "1_1") (pintype "bidirectional"))
    )
    (net (code "3") (name "/AFE_SDA1") (class "Default")
      (node (ref "D2") (pin "4") (pinfunction "I/O3_4") (pintype "bidirectional"))
      (node (ref "IC2") (pin "3") (pinfunction "SDA_3") (pintype "bidirectional"))
      (node (ref "J3") (pin "34") (pinfunction "34_34") (pintype "bidirectional"))
      (node (ref "TP5") (pin "1") (pinfunction "1_1") (pintype "bidirectional"))
    )
    (net (code "4") (name "/AFE_SDA2") (class "Default")
      (node (ref "D1") (pin "4") (pinfunction "I/O3_4") (pintype "bidirectional"))
      (node (ref "IC1") (pin "3") (pinfunction "SDA_3") (pintype "bidirectional"))
      (node (ref "J4") (pin "34") (pinfunction "34_34") (pintype "bidirectional"))
      (node (ref "TP1") (pin "1") (pinfunction "1_1") (pintype "bidirectional"))
    )
    (net (code "5") (name "/FFORCE_N00") (class "Default")
      (node (ref "J1") (pin "2") (pinfunction "2_2") (pintype "bidirectional"))
      (node (ref "J4") (pin "36") (pinfunction "36_36") (pintype "bidirectional"))
    )
    (net (code "6") (name "/FFORCE_N01") (class "Default")
      (node (ref "J2") (pin "9") (pinfunction "9_9") (pintype "bidirectional"))
      (node (ref "J4") (pin "38") (pinfunction "38_38") (pintype "bidirectional"))
    )
    (net (code "7") (name "/FFORCE_N02") (class "Default")
      (node (ref "J1") (pin "6") (pinfunction "6_6") (pintype "bidirectional"))
      (node (ref "J4") (pin "40") (pinfunction "40_40") (pintype "bidirectional"))
    )
    (net (code "8") (name "/FFORCE_N03") (class "Default")
      (node (ref "J2") (pin "5") (pinfunction "5_5") (pintype "bidirectional"))
      (node (ref "J4") (pin "42") (pinfunction "42_42") (pintype "bidirectional"))
    )
    (net (code "9") (name "/FFORCE_N04") (class "Default")
      (node (ref "J4") (pin "44") (pinfunction "44_44") (pintype "bidirectional"))
      (node (ref "J5") (pin "2") (pinfunction "2_2") (pintype "bidirectional"))
    )
    (net (code "10") (name "/FFORCE_N05") (class "Default")
      (node (ref "J4") (pin "46") (pinfunction "46_46") (pintype "bidirectional"))
      (node (ref "J6") (pin "9") (pinfunction "9_9") (pintype "bidirectional"))
    )
    (net (code "11") (name "/FFORCE_N06") (class "Default")
      (node (ref "J4") (pin "48") (pinfunction "48_48") (pintype "bidirectional"))
      (node (ref "J5") (pin "6") (pinfunction "6_6") (pintype "bidirectional"))
    )
    (net (code "12") (name "/FFORCE_N07") (class "Default")
      (node (ref "J4") (pin "50") (pinfunction "50_50") (pintype "bidirectional"))
      (node (ref "J6") (pin "5") (pinfunction "5_5") (pintype "bidirectional"))
    )
    (net (code "13") (name "/FFORCE_N08") (class "Default")
      (node (ref "J4") (pin "52") (pinfunction "52_52") (pintype "bidirectional"))
      (node (ref "J7") (pin "2") (pinfunction "2_2") (pintype "bidirectional"))
    )
    (net (code "14") (name "/FFORCE_N09") (class "Default")
      (node (ref "J4") (pin "54") (pinfunction "54_54") (pintype "bidirectional"))
      (node (ref "J8") (pin "9") (pinfunction "9_9") (pintype "bidirectional"))
    )
    (net (code "15") (name "/FFORCE_N10") (class "Default")
      (node (ref "J4") (pin "56") (pinfunction "56_56") (pintype "bidirectional"))
      (node (ref "J7") (pin "6") (pinfunction "6_6") (pintype "bidirectional"))
    )
    (net (code "16") (name "/FFORCE_N11") (class "Default")
      (node (ref "J4") (pin "58") (pinfunction "58_58") (pintype "bidirectional"))
      (node (ref "J8") (pin "5") (pinfunction "5_5") (pintype "bidirectional"))
    )
    (net (code "17") (name "/FFORCE_N12") (class "Default")
      (node (ref "J4") (pin "60") (pinfunction "60_60") (pintype "bidirectional"))
      (node (ref "J9") (pin "2") (pinfunction "2_2") (pintype "bidirectional"))
    )
    (net (code "18") (name "/FFORCE_N13") (class "Default")
      (node (ref "J10") (pin "9") (pinfunction "9_9") (pintype "bidirectional"))
      (node (ref "J4") (pin "62") (pinfunction "62_62") (pintype "bidirectional"))
    )
    (net (code "19") (name "/FFORCE_N14") (class "Default")
      (node (ref "J4") (pin "64") (pinfunction "64_64") (pintype "bidirectional"))
      (node (ref "J9") (pin "6") (pinfunction "6_6") (pintype "bidirectional"))
    )
    (net (code "20") (name "/FFORCE_N15") (class "Default")
      (node (ref "J10") (pin "5") (pinfunction "5_5") (pintype "bidirectional"))
      (node (ref "J4") (pin "66") (pinfunction "66_66") (pintype "bidirectional"))
    )
    (net (code "21") (name "/FFORCE_P00") (class "Default")
      (node (ref "J1") (pin "5") (pinfunction "5_5") (pintype "bidirectional"))
      (node (ref "J4") (pin "37") (pinfunction "37_37") (pintype "bidirectional"))
    )
    (net (code "22") (name "/FFORCE_P01") (class "Default")
      (node (ref "J2") (pin "6") (pinfunction "6_6") (pintype "bidirectional"))
      (node (ref "J4") (pin "39") (pinfunction "39_39") (pintype "bidirectional"))
    )
    (net (code "23") (name "/FFORCE_P02") (class "Default")
      (node (ref "J1") (pin "9") (pinfunction "9_9") (pintype "bidirectional"))
      (node (ref "J4") (pin "41") (pinfunction "41_41") (pintype "bidirectional"))
    )
    (net (code "24") (name "/FFORCE_P03") (class "Default")
      (node (ref "J2") (pin "2") (pinfunction "2_2") (pintype "bidirectional"))
      (node (ref "J4") (pin "43") (pinfunction "43_43") (pintype "bidirectional"))
    )
    (net (code "25") (name "/FFORCE_P04") (class "Default")
      (node (ref "J4") (pin "45") (pinfunction "45_45") (pintype "bidirectional"))
      (node (ref "J5") (pin "5") (pinfunction "5_5") (pintype "bidirectional"))
    )
    (net (code "26") (name "/FFORCE_P05") (class "Default")
      (node (ref "J4") (pin "47") (pinfunction "47_47") (pintype "bidirectional"))
      (node (ref "J6") (pin "6") (pinfunction "6_6") (pintype "bidirectional"))
    )
    (net (code "27") (name "/FFORCE_P06") (class "Default")
      (node (ref "J4") (pin "49") (pinfunction "49_49") (pintype "bidirectional"))
      (node (ref "J5") (pin "9") (pinfunction "9_9") (pintype "bidirectional"))
    )
    (net (code "28") (name "/FFORCE_P07") (class "Default")
      (node (ref "J4") (pin "51") (pinfunction "51_51") (pintype "bidirectional"))
      (node (ref "J6") (pin "2") (pinfunction "2_2") (pintype "bidirectional"))
    )
    (net (code "29") (name "/FFORCE_P08") (class "Default")
      (node (ref "J4") (pin "53") (pinfunction "53_53") (pintype "bidirectional"))
      (node (ref "J7") (pin "5") (pinfunction "5_5") (pintype "bidirectional"))
    )
    (net (code "30") (name "/FFORCE_P09") (class "Default")
      (node (ref "J4") (pin "55") (pinfunction "55_55") (pintype "bidirectional"))
      (node (ref "J8") (pin "6") (pinfunction "6_6") (pintype "bidirectional"))
    )
    (net (code "31") (name "/FFORCE_P10") (class "Default")
      (node (ref "J4") (pin "57") (pinfunction "57_57") (pintype "bidirectional"))
      (node (ref "J7") (pin "9") (pinfunction "9_9") (pintype "bidirectional"))
    )
    (net (code "32") (name "/FFORCE_P11") (class "Default")
      (node (ref "J4") (pin "59") (pinfunction "59_59") (pintype "bidirectional"))
      (node (ref "J8") (pin "2") (pinfunction "2_2") (pintype "bidirectional"))
    )
    (net (code "33") (name "/FFORCE_P12") (class "Default")
      (node (ref "J4") (pin "61") (pinfunction "61_61") (pintype "bidirectional"))
      (node (ref "J9") (pin "5") (pinfunction "5_5") (pintype "bidirectional"))
    )
    (net (code "34") (name "/FFORCE_P13") (class "Default")
      (node (ref "J10") (pin "6") (pinfunction "6_6") (pintype "bidirectional"))
      (node (ref "J4") (pin "63") (pinfunction "63_63") (pintype "bidirectional"))
    )
    (net (code "35") (name "/FFORCE_P14") (class "Default")
      (node (ref "J4") (pin "65") (pinfunction "65_65") (pintype "bidirectional"))
      (node (ref "J9") (pin "9") (pinfunction "9_9") (pintype "bidirectional"))
    )
    (net (code "36") (name "/FFORCE_P15") (class "Default")
      (node (ref "J10") (pin "2") (pinfunction "2_2") (pintype "bidirectional"))
      (node (ref "J4") (pin "67") (pinfunction "67_67") (pintype "bidirectional"))
    )
    (net (code "37") (name "/FRTDIN_N00") (class "Default")
      (node (ref "J1") (pin "3") (pinfunction "3_3") (pintype "bidirectional"))
      (node (ref "J4") (pin "2") (pinfunction "2_2") (pintype "bidirectional"))
    )
    (net (code "38") (name "/FRTDIN_N01") (class "Default")
      (node (ref "J2") (pin "8") (pinfunction "8_8") (pintype "bidirectional"))
      (node (ref "J4") (pin "4") (pinfunction "4_4") (pintype "bidirectional"))
    )
    (net (code "39") (name "/FRTDIN_N02") (class "Default")
      (node (ref "J1") (pin "7") (pinfunction "7_7") (pintype "bidirectional"))
      (node (ref "J4") (pin "6") (pinfunction "6_6") (pintype "bidirectional"))
    )
    (net (code "40") (name "/FRTDIN_N03") (class "Default")
      (node (ref "J2") (pin "4") (pinfunction "4_4") (pintype "bidirectional"))
      (node (ref "J4") (pin "8") (pinfunction "8_8") (pintype "bidirectional"))
    )
    (net (code "41") (name "/FRTDIN_N04") (class "Default")
      (node (ref "J4") (pin "10") (pinfunction "10_10") (pintype "bidirectional"))
      (node (ref "J5") (pin "3") (pinfunction "3_3") (pintype "bidirectional"))
    )
    (net (code "42") (name "/FRTDIN_N05") (class "Default")
      (node (ref "J4") (pin "12") (pinfunction "12_12") (pintype "bidirectional"))
      (node (ref "J6") (pin "8") (pinfunction "8_8") (pintype "bidirectional"))
    )
    (net (code "43") (name "/FRTDIN_N06") (class "Default")
      (node (ref "J4") (pin "14") (pinfunction "14_14") (pintype "bidirectional"))
      (node (ref "J5") (pin "7") (pinfunction "7_7") (pintype "bidirectional"))
    )
    (net (code "44") (name "/FRTDIN_N07") (class "Default")
      (node (ref "J4") (pin "16") (pinfunction "16_16") (pintype "bidirectional"))
      (node (ref "J6") (pin "4") (pinfunction "4_4") (pintype "bidirectional"))
    )
    (net (code "45") (name "/FRTDIN_N08") (class "Default")
      (node (ref "J4") (pin "18") (pinfunction "18_18") (pintype "bidirectional"))
      (node (ref "J7") (pin "3") (pinfunction "3_3") (pintype "bidirectional"))
    )
    (net (code "46") (name "/FRTDIN_N09") (class "Default")
      (node (ref "J4") (pin "20") (pinfunction "20_20") (pintype "bidirectional"))
      (node (ref "J8") (pin "8") (pinfunction "8_8") (pintype "bidirectional"))
    )
    (net (code "47") (name "/FRTDIN_N10") (class "Default")
      (node (ref "J4") (pin "22") (pinfunction "22_22") (pintype "bidirectional"))
      (node (ref "J7") (pin "7") (pinfunction "7_7") (pintype "bidirectional"))
    )
    (net (code "48") (name "/FRTDIN_N11") (class "Default")
      (node (ref "J4") (pin "24") (pinfunction "24_24") (pintype "bidirectional"))
      (node (ref "J8") (pin "4") (pinfunction "4_4") (pintype "bidirectional"))
    )
    (net (code "49") (name "/FRTDIN_N12") (class "Default")
      (node (ref "J4") (pin "26") (pinfunction "26_26") (pintype "bidirectional"))
      (node (ref "J9") (pin "3") (pinfunction "3_3") (pintype "bidirectional"))
    )
    (net (code "50") (name "/FRTDIN_N13") (class "Default")
      (node (ref "J10") (pin "8") (pinfunction "8_8") (pintype "bidirectional"))
      (node (ref "J4") (pin "28") (pinfunction "28_28") (pintype "bidirectional"))
    )
    (net (code "51") (name "/FRTDIN_N14") (class "Default")
      (node (ref "J4") (pin "30") (pinfunction "30_30") (pintype "bidirectional"))
      (node (ref "J9") (pin "7") (pinfunction "7_7") (pintype "bidirectional"))
    )
    (net (code "52") (name "/FRTDIN_N15") (class "Default")
      (node (ref "J10") (pin "4") (pinfunction "4_4") (pintype "bidirectional"))
      (node (ref "J4") (pin "32") (pinfunction "32_32") (pintype "bidirectional"))
    )
    (net (code "53") (name "/FRTDIN_P00") (class "Default")
      (node (ref "J1") (pin "4") (pinfunction "4_4") (pintype "bidirectional"))
      (node (ref "J4") (pin "3") (pinfunction "3_3") (pintype "bidirectional"))
    )
    (net (code "54") (name "/FRTDIN_P01") (class "Default")
      (node (ref "J2") (pin "7") (pinfunction "7_7") (pintype "bidirectional"))
      (node (ref "J4") (pin "5") (pinfunction "5_5") (pintype "bidirectional"))
    )
    (net (code "55") (name "/FRTDIN_P02") (class "Default")
      (node (ref "J1") (pin "8") (pinfunction "8_8") (pintype "bidirectional"))
      (node (ref "J4") (pin "7") (pinfunction "7_7") (pintype "bidirectional"))
    )
    (net (code "56") (name "/FRTDIN_P03") (class "Default")
      (node (ref "J2") (pin "3") (pinfunction "3_3") (pintype "bidirectional"))
      (node (ref "J4") (pin "9") (pinfunction "9_9") (pintype "bidirectional"))
    )
    (net (code "57") (name "/FRTDIN_P04") (class "Default")
      (node (ref "J4") (pin "11") (pinfunction "11_11") (pintype "bidirectional"))
      (node (ref "J5") (pin "4") (pinfunction "4_4") (pintype "bidirectional"))
    )
    (net (code "58") (name "/FRTDIN_P05") (class "Default")
      (node (ref "J4") (pin "13") (pinfunction "13_13") (pintype "bidirectional"))
      (node (ref "J6") (pin "7") (pinfunction "7_7") (pintype "bidirectional"))
    )
    (net (code "59") (name "/FRTDIN_P06") (class "Default")
      (node (ref "J4") (pin "15") (pinfunction "15_15") (pintype "bidirectional"))
      (node (ref "J5") (pin "8") (pinfunction "8_8") (pintype "bidirectional"))
    )
    (net (code "60") (name "/FRTDIN_P07") (class "Default")
      (node (ref "J4") (pin "17") (pinfunction "17_17") (pintype "bidirectional"))
      (node (ref "J6") (pin "3") (pinfunction "3_3") (pintype "bidirectional"))
    )
    (net (code "61") (name "/FRTDIN_P08") (class "Default")
      (node (ref "J4") (pin "19") (pinfunction "19_19") (pintype "bidirectional"))
      (node (ref "J7") (pin "4") (pinfunction "4_4") (pintype "bidirectional"))
    )
    (net (code "62") (name "/FRTDIN_P09") (class "Default")
      (node (ref "J4") (pin "21") (pinfunction "21_21") (pintype "bidirectional"))
      (node (ref "J8") (pin "7") (pinfunction "7_7") (pintype "bidirectional"))
    )
    (net (code "63") (name "/FRTDIN_P10") (class "Default")
      (node (ref "J4") (pin "23") (pinfunction "23_23") (pintype "bidirectional"))
      (node (ref "J7") (pin "8") (pinfunction "8_8") (pintype "bidirectional"))
    )
    (net (code "64") (name "/FRTDIN_P11") (class "Default")
      (node (ref "J4") (pin "25") (pinfunction "25_25") (pintype "bidirectional"))
      (node (ref "J8") (pin "3") (pinfunction "3_3") (pintype "bidirectional"))
    )
    (net (code "65") (name "/FRTDIN_P12") (class "Default")
      (node (ref "J4") (pin "27") (pinfunction "27_27") (pintype "bidirectional"))
      (node (ref "J9") (pin "4") (pinfunction "4_4") (pintype "bidirectional"))
    )
    (net (code "66") (name "/FRTDIN_P13") (class "Default")
      (node (ref "J10") (pin "7") (pinfunction "7_7") (pintype "bidirectional"))
      (node (ref "J4") (pin "29") (pinfunction "29_29") (pintype "bidirectional"))
    )
    (net (code "67") (name "/FRTDIN_P14") (class "Default")
      (node (ref "J4") (pin "31") (pinfunction "31_31") (pintype "bidirectional"))
      (node (ref "J9") (pin "8") (pinfunction "8_8") (pintype "bidirectional"))
    )
    (net (code "68") (name "/FRTDIN_P15") (class "Default")
      (node (ref "J10") (pin "3") (pinfunction "3_3") (pintype "bidirectional"))
      (node (ref "J4") (pin "33") (pinfunction "33_33") (pintype "bidirectional"))
    )
    (net (code "69") (name "/PFORCE_N00") (class "Default")
      (node (ref "J11") (pin "2") (pinfunction "2_2") (pintype "bidirectional"))
      (node (ref "J13") (pin "1") (pinfunction "1_1") (pintype "bidirectional"))
    )
    (net (code "70") (name "/PFORCE_N01") (class "Default")
      (node (ref "J12") (pin "2") (pinfunction "2_2") (pintype "bidirectional"))
      (node (ref "J14") (pin "1") (pinfunction "1_1") (pintype "bidirectional"))
    )
    (net (code "71") (name "/PFORCE_N02") (class "Default")
      (node (ref "J11") (pin "6") (pinfunction "6_6") (pintype "bidirectional"))
      (node (ref "J21") (pin "1") (pinfunction "1_1") (pintype "bidirectional"))
    )
    (net (code "72") (name "/PFORCE_N03") (class "Default")
      (node (ref "J12") (pin "6") (pinfunction "6_6") (pintype "bidirectional"))
      (node (ref "J22") (pin "1") (pinfunction "1_1") (pintype "bidirectional"))
    )
    (net (code "73") (name "/PFORCE_N04") (class "Default")
      (node (ref "J29") (pin "2") (pinfunction "2_2") (pintype "bidirectional"))
      (node (ref "J31") (pin "1") (pinfunction "1_1") (pintype "bidirectional"))
    )
    (net (code "74") (name "/PFORCE_N05") (class "Default")
      (node (ref "J30") (pin "2") (pinfunction "2_2") (pintype "bidirectional"))
      (node (ref "J32") (pin "1") (pinfunction "1_1") (pintype "bidirectional"))
    )
    (net (code "75") (name "/PFORCE_N06") (class "Default")
      (node (ref "J29") (pin "6") (pinfunction "6_6") (pintype "bidirectional"))
      (node (ref "J39") (pin "1") (pinfunction "1_1") (pintype "bidirectional"))
    )
    (net (code "76") (name "/PFORCE_N07") (class "Default")
      (node (ref "J30") (pin "9") (pinfunction "9_9") (pintype "bidirectional"))
      (node (ref "J46") (pin "1") (pinfunction "1_1") (pintype "bidirectional"))
    )
    (net (code "77") (name "/PFORCE_N08") (class "Default")
      (node (ref "J47") (pin "2") (pinfunction "2_2") (pintype "bidirectional"))
      (node (ref "J49") (pin "1") (pinfunction "1_1") (pintype "bidirectional"))
    )
    (net (code "78") (name "/PFORCE_N09") (class "Default")
      (node (ref "J48") (pin "2") (pinfunction "2_2") (pintype "bidirectional"))
      (node (ref "J50") (pin "1") (pinfunction "1_1") (pintype "bidirectional"))
    )
    (net (code "79") (name "/PFORCE_N10") (class "Default")
      (node (ref "J47") (pin "6") (pinfunction "6_6") (pintype "bidirectional"))
      (node (ref "J57") (pin "1") (pinfunction "1_1") (pintype "bidirectional"))
    )
    (net (code "80") (name "/PFORCE_N11") (class "Default")
      (node (ref "J48") (pin "9") (pinfunction "9_9") (pintype "bidirectional"))
      (node (ref "J64") (pin "1") (pinfunction "1_1") (pintype "bidirectional"))
    )
    (net (code "81") (name "/PFORCE_N12") (class "Default")
      (node (ref "J65") (pin "2") (pinfunction "2_2") (pintype "bidirectional"))
      (node (ref "J67") (pin "1") (pinfunction "1_1") (pintype "bidirectional"))
    )
    (net (code "82") (name "/PFORCE_N13") (class "Default")
      (node (ref "J66") (pin "2") (pinfunction "2_2") (pintype "bidirectional"))
      (node (ref "J68") (pin "1") (pinfunction "1_1") (pintype "bidirectional"))
    )
    (net (code "83") (name "/PFORCE_N14") (class "Default")
      (node (ref "J65") (pin "6") (pinfunction "6_6") (pintype "bidirectional"))
      (node (ref "J75") (pin "1") (pinfunction "1_1") (pintype "bidirectional"))
    )
    (net (code "84") (name "/PFORCE_N15") (class "Default")
      (node (ref "J66") (pin "9") (pinfunction "9_9") (pintype "bidirectional"))
      (node (ref "J82") (pin "1") (pinfunction "1_1") (pintype "bidirectional"))
    )
    (net (code "85") (name "/PFORCE_P00") (class "Default")
      (node (ref "J11") (pin "5") (pinfunction "5_5") (pintype "bidirectional"))
      (node (ref "J19") (pin "1") (pinfunction "1_1") (pintype "bidirectional"))
    )
    (net (code "86") (name "/PFORCE_P01") (class "Default")
      (node (ref "J12") (pin "5") (pinfunction "5_5") (pintype "bidirectional"))
      (node (ref "J20") (pin "1") (pinfunction "1_1") (pintype "bidirectional"))
    )
    (net (code "87") (name "/PFORCE_P02") (class "Default")
      (node (ref "J11") (pin "9") (pinfunction "9_9") (pintype "bidirectional"))
      (node (ref "J27") (pin "1") (pinfunction "1_1") (pintype "bidirectional"))
    )
    (net (code "88") (name "/PFORCE_P03") (class "Default")
      (node (ref "J12") (pin "9") (pinfunction "9_9") (pintype "bidirectional"))
      (node (ref "J28") (pin "1") (pinfunction "1_1") (pintype "bidirectional"))
    )
    (net (code "89") (name "/PFORCE_P04") (class "Default")
      (node (ref "J29") (pin "5") (pinfunction "5_5") (pintype "bidirectional"))
      (node (ref "J37") (pin "1") (pinfunction "1_1") (pintype "bidirectional"))
    )
    (net (code "90") (name "/PFORCE_P05") (class "Default")
      (node (ref "J30") (pin "5") (pinfunction "5_5") (pintype "bidirectional"))
      (node (ref "J38") (pin "1") (pinfunction "1_1") (pintype "bidirectional"))
    )
    (net (code "91") (name "/PFORCE_P06") (class "Default")
      (node (ref "J29") (pin "9") (pinfunction "9_9") (pintype "bidirectional"))
      (node (ref "J45") (pin "1") (pinfunction "1_1") (pintype "bidirectional"))
    )
    (net (code "92") (name "/PFORCE_P07") (class "Default")
      (node (ref "J30") (pin "6") (pinfunction "6_6") (pintype "bidirectional"))
      (node (ref "J40") (pin "1") (pinfunction "1_1") (pintype "bidirectional"))
    )
    (net (code "93") (name "/PFORCE_P08") (class "Default")
      (node (ref "J47") (pin "5") (pinfunction "5_5") (pintype "bidirectional"))
      (node (ref "J55") (pin "1") (pinfunction "1_1") (pintype "bidirectional"))
    )
    (net (code "94") (name "/PFORCE_P09") (class "Default")
      (node (ref "J48") (pin "5") (pinfunction "5_5") (pintype "bidirectional"))
      (node (ref "J56") (pin "1") (pinfunction "1_1") (pintype "bidirectional"))
    )
    (net (code "95") (name "/PFORCE_P10") (class "Default")
      (node (ref "J47") (pin "9") (pinfunction "9_9") (pintype "bidirectional"))
      (node (ref "J63") (pin "1") (pinfunction "1_1") (pintype "bidirectional"))
    )
    (net (code "96") (name "/PFORCE_P11") (class "Default")
      (node (ref "J48") (pin "6") (pinfunction "6_6") (pintype "bidirectional"))
      (node (ref "J58") (pin "1") (pinfunction "1_1") (pintype "bidirectional"))
    )
    (net (code "97") (name "/PFORCE_P12") (class "Default")
      (node (ref "J65") (pin "5") (pinfunction "5_5") (pintype "bidirectional"))
      (node (ref "J73") (pin "1") (pinfunction "1_1") (pintype "bidirectional"))
    )
    (net (code "98") (name "/PFORCE_P13") (class "Default")
      (node (ref "J66") (pin "5") (pinfunction "5_5") (pintype "bidirectional"))
      (node (ref "J74") (pin "1") (pinfunction "1_1") (pintype "bidirectional"))
    )
    (net (code "99") (name "/PFORCE_P14") (class "Default")
      (node (ref "J65") (pin "9") (pinfunction "9_9") (pintype "bidirectional"))
      (node (ref "J81") (pin "1") (pinfunction "1_1") (pintype "bidirectional"))
    )
    (net (code "100") (name "/PFORCE_P15") (class "Default")
      (node (ref "J66") (pin "6") (pinfunction "6_6") (pintype "bidirectional"))
      (node (ref "J76") (pin "1") (pinfunction "1_1") (pintype "bidirectional"))
    )
    (net (code "101") (name "/PRTDIN_N00") (class "Default")
      (node (ref "J11") (pin "3") (pinfunction "3_3") (pintype "bidirectional"))
      (node (ref "J15") (pin "1") (pinfunction "1_1") (pintype "bidirectional"))
    )
    (net (code "102") (name "/PRTDIN_N01") (class "Default")
      (node (ref "J12") (pin "3") (pinfunction "3_3") (pintype "bidirectional"))
      (node (ref "J16") (pin "1") (pinfunction "1_1") (pintype "bidirectional"))
    )
    (net (code "103") (name "/PRTDIN_N02") (class "Default")
      (node (ref "J11") (pin "7") (pinfunction "7_7") (pintype "bidirectional"))
      (node (ref "J23") (pin "1") (pinfunction "1_1") (pintype "bidirectional"))
    )
    (net (code "104") (name "/PRTDIN_N03") (class "Default")
      (node (ref "J12") (pin "7") (pinfunction "7_7") (pintype "bidirectional"))
      (node (ref "J24") (pin "1") (pinfunction "1_1") (pintype "bidirectional"))
    )
    (net (code "105") (name "/PRTDIN_N04") (class "Default")
      (node (ref "J29") (pin "3") (pinfunction "3_3") (pintype "bidirectional"))
      (node (ref "J33") (pin "1") (pinfunction "1_1") (pintype "bidirectional"))
    )
    (net (code "106") (name "/PRTDIN_N05") (class "Default")
      (node (ref "J30") (pin "3") (pinfunction "3_3") (pintype "bidirectional"))
      (node (ref "J34") (pin "1") (pinfunction "1_1") (pintype "bidirectional"))
    )
    (net (code "107") (name "/PRTDIN_N06") (class "Default")
      (node (ref "J29") (pin "7") (pinfunction "7_7") (pintype "bidirectional"))
      (node (ref "J41") (pin "1") (pinfunction "1_1") (pintype "bidirectional"))
    )
    (net (code "108") (name "/PRTDIN_N07") (class "Default")
      (node (ref "J30") (pin "8") (pinfunction "8_8") (pintype "bidirectional"))
      (node (ref "J44") (pin "1") (pinfunction "1_1") (pintype "bidirectional"))
    )
    (net (code "109") (name "/PRTDIN_N08") (class "Default")
      (node (ref "J47") (pin "3") (pinfunction "3_3") (pintype "bidirectional"))
      (node (ref "J51") (pin "1") (pinfunction "1_1") (pintype "bidirectional"))
    )
    (net (code "110") (name "/PRTDIN_N09") (class "Default")
      (node (ref "J48") (pin "3") (pinfunction "3_3") (pintype "bidirectional"))
      (node (ref "J52") (pin "1") (pinfunction "1_1") (pintype "bidirectional"))
    )
    (net (code "111") (name "/PRTDIN_N10") (class "Default")
      (node (ref "J47") (pin "7") (pinfunction "7_7") (pintype "bidirectional"))
      (node (ref "J59") (pin "1") (pinfunction "1_1") (pintype "bidirectional"))
    )
    (net (code "112") (name "/PRTDIN_N11") (class "Default")
      (node (ref "J48") (pin "8") (pinfunction "8_8") (pintype "bidirectional"))
      (node (ref "J62") (pin "1") (pinfunction "1_1") (pintype "bidirectional"))
    )
    (net (code "113") (name "/PRTDIN_N12") (class "Default")
      (node (ref "J65") (pin "3") (pinfunction "3_3") (pintype "bidirectional"))
      (node (ref "J69") (pin "1") (pinfunction "1_1") (pintype "bidirectional"))
    )
    (net (code "114") (name "/PRTDIN_N13") (class "Default")
      (node (ref "J66") (pin "3") (pinfunction "3_3") (pintype "bidirectional"))
      (node (ref "J70") (pin "1") (pinfunction "1_1") (pintype "bidirectional"))
    )
    (net (code "115") (name "/PRTDIN_N14") (class "Default")
      (node (ref "J65") (pin "7") (pinfunction "7_7") (pintype "bidirectional"))
      (node (ref "J77") (pin "1") (pinfunction "1_1") (pintype "bidirectional"))
    )
    (net (code "116") (name "/PRTDIN_N15") (class "Default")
      (node (ref "J66") (pin "8") (pinfunction "8_8") (pintype "bidirectional"))
      (node (ref "J80") (pin "1") (pinfunction "1_1") (pintype "bidirectional"))
    )
    (net (code "117") (name "/PRTDIN_P00") (class "Default")
      (node (ref "J11") (pin "4") (pinfunction "4_4") (pintype "bidirectional"))
      (node (ref "J17") (pin "1") (pinfunction "1_1") (pintype "bidirectional"))
    )
    (net (code "118") (name "/PRTDIN_P01") (class "Default")
      (node (ref "J12") (pin "4") (pinfunction "4_4") (pintype "bidirectional"))
      (node (ref "J18") (pin "1") (pinfunction "1_1") (pintype "bidirectional"))
    )
    (net (code "119") (name "/PRTDIN_P02") (class "Default")
      (node (ref "J11") (pin "8") (pinfunction "8_8") (pintype "bidirectional"))
      (node (ref "J25") (pin "1") (pinfunction "1_1") (pintype "bidirectional"))
    )
    (net (code "120") (name "/PRTDIN_P03") (class "Default")
      (node (ref "J12") (pin "8") (pinfunction "8_8") (pintype "bidirectional"))
      (node (ref "J26") (pin "1") (pinfunction "1_1") (pintype "bidirectional"))
    )
    (net (code "121") (name "/PRTDIN_P04") (class "Default")
      (node (ref "J29") (pin "4") (pinfunction "4_4") (pintype "bidirectional"))
      (node (ref "J35") (pin "1") (pinfunction "1_1") (pintype "bidirectional"))
    )
    (net (code "122") (name "/PRTDIN_P05") (class "Default")
      (node (ref "J30") (pin "4") (pinfunction "4_4") (pintype "bidirectional"))
      (node (ref "J36") (pin "1") (pinfunction "1_1") (pintype "bidirectional"))
    )
    (net (code "123") (name "/PRTDIN_P06") (class "Default")
      (node (ref "J29") (pin "8") (pinfunction "8_8") (pintype "bidirectional"))
      (node (ref "J43") (pin "1") (pinfunction "1_1") (pintype "bidirectional"))
    )
    (net (code "124") (name "/PRTDIN_P07") (class "Default")
      (node (ref "J30") (pin "7") (pinfunction "7_7") (pintype "bidirectional"))
      (node (ref "J42") (pin "1") (pinfunction "1_1") (pintype "bidirectional"))
    )
    (net (code "125") (name "/PRTDIN_P08") (class "Default")
      (node (ref "J47") (pin "4") (pinfunction "4_4") (pintype "bidirectional"))
      (node (ref "J53") (pin "1") (pinfunction "1_1") (pintype "bidirectional"))
    )
    (net (code "126") (name "/PRTDIN_P09") (class "Default")
      (node (ref "J48") (pin "4") (pinfunction "4_4") (pintype "bidirectional"))
      (node (ref "J54") (pin "1") (pinfunction "1_1") (pintype "bidirectional"))
    )
    (net (code "127") (name "/PRTDIN_P10") (class "Default")
      (node (ref "J47") (pin "8") (pinfunction "8_8") (pintype "bidirectional"))
      (node (ref "J61") (pin "1") (pinfunction "1_1") (pintype "bidirectional"))
    )
    (net (code "128") (name "/PRTDIN_P11") (class "Default")
      (node (ref "J48") (pin "7") (pinfunction "7_7") (pintype "bidirectional"))
      (node (ref "J60") (pin "1") (pinfunction "1_1") (pintype "bidirectional"))
    )
    (net (code "129") (name "/PRTDIN_P12") (class "Default")
      (node (ref "J65") (pin "4") (pinfunction "4_4") (pintype "bidirectional"))
      (node (ref "J71") (pin "1") (pinfunction "1_1") (pintype "bidirectional"))
    )
    (net (code "130") (name "/PRTDIN_P13") (class "Default")
      (node (ref "J66") (pin "4") (pinfunction "4_4") (pintype "bidirectional"))
      (node (ref "J72") (pin "1") (pinfunction "1_1") (pintype "bidirectional"))
    )
    (net (code "131") (name "/PRTDIN_P14") (class "Default")
      (node (ref "J65") (pin "8") (pinfunction "8_8") (pintype "bidirectional"))
      (node (ref "J79") (pin "1") (pinfunction "1_1") (pintype "bidirectional"))
    )
    (net (code "132") (name "/PRTDIN_P15") (class "Default")
      (node (ref "J66") (pin "7") (pinfunction "7_7") (pintype "bidirectional"))
      (node (ref "J78") (pin "1") (pinfunction "1_1") (pintype "bidirectional"))
    )
    (net (code "133") (name "/TFORCE_N00") (class "Default")
      (node (ref "J3") (pin "36") (pinfunction "36_36") (pintype "bidirectional"))
      (node (ref "P1") (pin "4") (pinfunction "4_4") (pintype "passive"))
    )
    (net (code "134") (name "/TFORCE_N01") (class "Default")
      (node (ref "J3") (pin "38") (pinfunction "38_38") (pintype "bidirectional"))
      (node (ref "P3") (pin "4") (pinfunction "4_4") (pintype "passive"))
    )
    (net (code "135") (name "/TFORCE_N02") (class "Default")
      (node (ref "J3") (pin "40") (pinfunction "40_40") (pintype "bidirectional"))
      (node (ref "P5") (pin "4") (pinfunction "4_4") (pintype "passive"))
    )
    (net (code "136") (name "/TFORCE_N03") (class "Default")
      (node (ref "J3") (pin "42") (pinfunction "42_42") (pintype "bidirectional"))
      (node (ref "P7") (pin "4") (pinfunction "4_4") (pintype "passive"))
    )
    (net (code "137") (name "/TFORCE_N04") (class "Default")
      (node (ref "J3") (pin "44") (pinfunction "44_44") (pintype "bidirectional"))
      (node (ref "P9") (pin "4") (pinfunction "4_4") (pintype "passive"))
    )
    (net (code "138") (name "/TFORCE_N05") (class "Default")
      (node (ref "J3") (pin "46") (pinfunction "46_46") (pintype "bidirectional"))
      (node (ref "P11") (pin "4") (pinfunction "4_4") (pintype "passive"))
    )
    (net (code "139") (name "/TFORCE_N06") (class "Default")
      (node (ref "J3") (pin "48") (pinfunction "48_48") (pintype "bidirectional"))
      (node (ref "P13") (pin "4") (pinfunction "4_4") (pintype "passive"))
    )
    (net (code "140") (name "/TFORCE_N07") (class "Default")
      (node (ref "J3") (pin "50") (pinfunction "50_50") (pintype "bidirectional"))
      (node (ref "P15") (pin "4") (pinfunction "4_4") (pintype "passive"))
    )
    (net (code "141") (name "/TFORCE_N08") (class "Default")
      (node (ref "J3") (pin "52") (pinfunction "52_52") (pintype "bidirectional"))
      (node (ref "P2") (pin "4") (pinfunction "4_4") (pintype "passive"))
    )
    (net (code "142") (name "/TFORCE_N09") (class "Default")
      (node (ref "J3") (pin "54") (pinfunction "54_54") (pintype "bidirectional"))
      (node (ref "P4") (pin "4") (pinfunction "4_4") (pintype "passive"))
    )
    (net (code "143") (name "/TFORCE_N10") (class "Default")
      (node (ref "J3") (pin "56") (pinfunction "56_56") (pintype "bidirectional"))
      (node (ref "P6") (pin "4") (pinfunction "4_4") (pintype "passive"))
    )
    (net (code "144") (name "/TFORCE_N11") (class "Default")
      (node (ref "J3") (pin "58") (pinfunction "58_58") (pintype "bidirectional"))
      (node (ref "P8") (pin "4") (pinfunction "4_4") (pintype "passive"))
    )
    (net (code "145") (name "/TFORCE_N12") (class "Default")
      (node (ref "J3") (pin "60") (pinfunction "60_60") (pintype "bidirectional"))
      (node (ref "P10") (pin "4") (pinfunction "4_4") (pintype "passive"))
    )
    (net (code "146") (name "/TFORCE_N13") (class "Default")
      (node (ref "J3") (pin "62") (pinfunction "62_62") (pintype "bidirectional"))
      (node (ref "P12") (pin "4") (pinfunction "4_4") (pintype "passive"))
    )
    (net (code "147") (name "/TFORCE_N14") (class "Default")
      (node (ref "J3") (pin "64") (pinfunction "64_64") (pintype "bidirectional"))
      (node (ref "P14") (pin "4") (pinfunction "4_4") (pintype "passive"))
    )
    (net (code "148") (name "/TFORCE_N15") (class "Default")
      (node (ref "J3") (pin "66") (pinfunction "66_66") (pintype "bidirectional"))
      (node (ref "P16") (pin "4") (pinfunction "4_4") (pintype "passive"))
    )
    (net (code "149") (name "/TFORCE_P00") (class "Default")
      (node (ref "J3") (pin "37") (pinfunction "37_37") (pintype "bidirectional"))
      (node (ref "P1") (pin "1") (pinfunction "1_1") (pintype "passive"))
    )
    (net (code "150") (name "/TFORCE_P01") (class "Default")
      (node (ref "J3") (pin "39") (pinfunction "39_39") (pintype "bidirectional"))
      (node (ref "P3") (pin "1") (pinfunction "1_1") (pintype "passive"))
    )
    (net (code "151") (name "/TFORCE_P02") (class "Default")
      (node (ref "J3") (pin "41") (pinfunction "41_41") (pintype "bidirectional"))
      (node (ref "P5") (pin "1") (pinfunction "1_1") (pintype "passive"))
    )
    (net (code "152") (name "/TFORCE_P03") (class "Default")
      (node (ref "J3") (pin "43") (pinfunction "43_43") (pintype "bidirectional"))
      (node (ref "P7") (pin "1") (pinfunction "1_1") (pintype "passive"))
    )
    (net (code "153") (name "/TFORCE_P04") (class "Default")
      (node (ref "J3") (pin "45") (pinfunction "45_45") (pintype "bidirectional"))
      (node (ref "P9") (pin "1") (pinfunction "1_1") (pintype "passive"))
    )
    (net (code "154") (name "/TFORCE_P05") (class "Default")
      (node (ref "J3") (pin "47") (pinfunction "47_47") (pintype "bidirectional"))
      (node (ref "P11") (pin "1") (pinfunction "1_1") (pintype "passive"))
    )
    (net (code "155") (name "/TFORCE_P06") (class "Default")
      (node (ref "J3") (pin "49") (pinfunction "49_49") (pintype "bidirectional"))
      (node (ref "P13") (pin "1") (pinfunction "1_1") (pintype "passive"))
    )
    (net (code "156") (name "/TFORCE_P07") (class "Default")
      (node (ref "J3") (pin "51") (pinfunction "51_51") (pintype "bidirectional"))
      (node (ref "P15") (pin "1") (pinfunction "1_1") (pintype "passive"))
    )
    (net (code "157") (name "/TFORCE_P08") (class "Default")
      (node (ref "J3") (pin "53") (pinfunction "53_53") (pintype "bidirectional"))
      (node (ref "P2") (pin "1") (pinfunction "1_1") (pintype "passive"))
    )
    (net (code "158") (name "/TFORCE_P09") (class "Default")
      (node (ref "J3") (pin "55") (pinfunction "55_55") (pintype "bidirectional"))
      (node (ref "P4") (pin "1") (pinfunction "1_1") (pintype "passive"))
    )
    (net (code "159") (name "/TFORCE_P10") (class "Default")
      (node (ref "J3") (pin "57") (pinfunction "57_57") (pintype "bidirectional"))
      (node (ref "P6") (pin "1") (pinfunction "1_1") (pintype "passive"))
    )
    (net (code "160") (name "/TFORCE_P11") (class "Default")
      (node (ref "J3") (pin "59") (pinfunction "59_59") (pintype "bidirectional"))
      (node (ref "P8") (pin "1") (pinfunction "1_1") (pintype "passive"))
    )
    (net (code "161") (name "/TFORCE_P12") (class "Default")
      (node (ref "J3") (pin "61") (pinfunction "61_61") (pintype "bidirectional"))
      (node (ref "P10") (pin "1") (pinfunction "1_1") (pintype "passive"))
    )
    (net (code "162") (name "/TFORCE_P13") (class "Default")
      (node (ref "J3") (pin "63") (pinfunction "63_63") (pintype "bidirectional"))
      (node (ref "P12") (pin "1") (pinfunction "1_1") (pintype "passive"))
    )
    (net (code "163") (name "/TFORCE_P14") (class "Default")
      (node (ref "J3") (pin "65") (pinfunction "65_65") (pintype "bidirectional"))
      (node (ref "P14") (pin "1") (pinfunction "1_1") (pintype "passive"))
    )
    (net (code "164") (name "/TFORCE_P15") (class "Default")
      (node (ref "J3") (pin "67") (pinfunction "67_67") (pintype "bidirectional"))
      (node (ref "P16") (pin "1") (pinfunction "1_1") (pintype "passive"))
    )
    (net (code "165") (name "/TRTDIN_N00") (class "Default")
      (node (ref "J3") (pin "2") (pinfunction "2_2") (pintype "bidirectional"))
      (node (ref "P1") (pin "3") (pinfunction "3_3") (pintype "passive"))
    )
    (net (code "166") (name "/TRTDIN_N01") (class "Default")
      (node (ref "J3") (pin "4") (pinfunction "4_4") (pintype "bidirectional"))
      (node (ref "P3") (pin "3") (pinfunction "3_3") (pintype "passive"))
    )
    (net (code "167") (name "/TRTDIN_N02") (class "Default")
      (node (ref "J3") (pin "6") (pinfunction "6_6") (pintype "bidirectional"))
      (node (ref "P5") (pin "3") (pinfunction "3_3") (pintype "passive"))
    )
    (net (code "168") (name "/TRTDIN_N03") (class "Default")
      (node (ref "J3") (pin "8") (pinfunction "8_8") (pintype "bidirectional"))
      (node (ref "P7") (pin "3") (pinfunction "3_3") (pintype "passive"))
    )
    (net (code "169") (name "/TRTDIN_N04") (class "Default")
      (node (ref "J3") (pin "10") (pinfunction "10_10") (pintype "bidirectional"))
      (node (ref "P9") (pin "3") (pinfunction "3_3") (pintype "passive"))
    )
    (net (code "170") (name "/TRTDIN_N05") (class "Default")
      (node (ref "J3") (pin "12") (pinfunction "12_12") (pintype "bidirectional"))
      (node (ref "P11") (pin "3") (pinfunction "3_3") (pintype "passive"))
    )
    (net (code "171") (name "/TRTDIN_N06") (class "Default")
      (node (ref "J3") (pin "14") (pinfunction "14_14") (pintype "bidirectional"))
      (node (ref "P13") (pin "3") (pinfunction "3_3") (pintype "passive"))
    )
    (net (code "172") (name "/TRTDIN_N07") (class "Default")
      (node (ref "J3") (pin "16") (pinfunction "16_16") (pintype "bidirectional"))
      (node (ref "P15") (pin "3") (pinfunction "3_3") (pintype "passive"))
    )
    (net (code "173") (name "/TRTDIN_N08") (class "Default")
      (node (ref "J3") (pin "18") (pinfunction "18_18") (pintype "bidirectional"))
      (node (ref "P2") (pin "3") (pinfunction "3_3") (pintype "passive"))
    )
    (net (code "174") (name "/TRTDIN_N09") (class "Default")
      (node (ref "J3") (pin "20") (pinfunction "20_20") (pintype "bidirectional"))
      (node (ref "P4") (pin "3") (pinfunction "3_3") (pintype "passive"))
    )
    (net (code "175") (name "/TRTDIN_N10") (class "Default")
      (node (ref "J3") (pin "22") (pinfunction "22_22") (pintype "bidirectional"))
      (node (ref "P6") (pin "3") (pinfunction "3_3") (pintype "passive"))
    )
    (net (code "176") (name "/TRTDIN_N11") (class "Default")
      (node (ref "J3") (pin "24") (pinfunction "24_24") (pintype "bidirectional"))
      (node (ref "P8") (pin "3") (pinfunction "3_3") (pintype "passive"))
    )
    (net (code "177") (name "/TRTDIN_N12") (class "Default")
      (node (ref "J3") (pin "26") (pinfunction "26_26") (pintype "bidirectional"))
      (node (ref "P10") (pin "3") (pinfunction "3_3") (pintype "passive"))
    )
    (net (code "178") (name "/TRTDIN_N13") (class "Default")
      (node (ref "J3") (pin "28") (pinfunction "28_28") (pintype "bidirectional"))
      (node (ref "P12") (pin "3") (pinfunction "3_3") (pintype "passive"))
    )
    (net (code "179") (name "/TRTDIN_N14") (class "Default")
      (node (ref "J3") (pin "30") (pinfunction "30_30") (pintype "bidirectional"))
      (node (ref "P14") (pin "3") (pinfunction "3_3") (pintype "passive"))
    )
    (net (code "180") (name "/TRTDIN_N15") (class "Default")
      (node (ref "J3") (pin "32") (pinfunction "32_32") (pintype "bidirectional"))
      (node (ref "P16") (pin "3") (pinfunction "3_3") (pintype "passive"))
    )
    (net (code "181") (name "/TRTDIN_P00") (class "Default")
      (node (ref "J3") (pin "3") (pinfunction "3_3") (pintype "bidirectional"))
      (node (ref "P1") (pin "2") (pinfunction "2_2") (pintype "passive"))
    )
    (net (code "182") (name "/TRTDIN_P01") (class "Default")
      (node (ref "J3") (pin "5") (pinfunction "5_5") (pintype "bidirectional"))
      (node (ref "P3") (pin "2") (pinfunction "2_2") (pintype "passive"))
    )
    (net (code "183") (name "/TRTDIN_P02") (class "Default")
      (node (ref "J3") (pin "7") (pinfunction "7_7") (pintype "bidirectional"))
      (node (ref "P5") (pin "2") (pinfunction "2_2") (pintype "passive"))
    )
    (net (code "184") (name "/TRTDIN_P03") (class "Default")
      (node (ref "J3") (pin "9") (pinfunction "9_9") (pintype "bidirectional"))
      (node (ref "P7") (pin "2") (pinfunction "2_2") (pintype "passive"))
    )
    (net (code "185") (name "/TRTDIN_P04") (class "Default")
      (node (ref "J3") (pin "11") (pinfunction "11_11") (pintype "bidirectional"))
      (node (ref "P9") (pin "2") (pinfunction "2_2") (pintype "passive"))
    )
    (net (code "186") (name "/TRTDIN_P05") (class "Default")
      (node (ref "J3") (pin "13") (pinfunction "13_13") (pintype "bidirectional"))
      (node (ref "P11") (pin "2") (pinfunction "2_2") (pintype "passive"))
    )
    (net (code "187") (name "/TRTDIN_P06") (class "Default")
      (node (ref "J3") (pin "15") (pinfunction "15_15") (pintype "bidirectional"))
      (node (ref "P13") (pin "2") (pinfunction "2_2") (pintype "passive"))
    )
    (net (code "188") (name "/TRTDIN_P07") (class "Default")
      (node (ref "J3") (pin "17") (pinfunction "17_17") (pintype "bidirectional"))
      (node (ref "P15") (pin "2") (pinfunction "2_2") (pintype "passive"))
    )
    (net (code "189") (name "/TRTDIN_P08") (class "Default")
      (node (ref "J3") (pin "19") (pinfunction "19_19") (pintype "bidirectional"))
      (node (ref "P2") (pin "2") (pinfunction "2_2") (pintype "passive"))
    )
    (net (code "190") (name "/TRTDIN_P09") (class "Default")
      (node (ref "J3") (pin "21") (pinfunction "21_21") (pintype "bidirectional"))
      (node (ref "P4") (pin "2") (pinfunction "2_2") (pintype "passive"))
    )
    (net (code "191") (name "/TRTDIN_P10") (class "Default")
      (node (ref "J3") (pin "23") (pinfunction "23_23") (pintype "bidirectional"))
      (node (ref "P6") (pin "2") (pinfunction "2_2") (pintype "passive"))
    )
    (net (code "192") (name "/TRTDIN_P11") (class "Default")
      (node (ref "J3") (pin "25") (pinfunction "25_25") (pintype "bidirectional"))
      (node (ref "P8") (pin "2") (pinfunction "2_2") (pintype "passive"))
    )
    (net (code "193") (name "/TRTDIN_P12") (class "Default")
      (node (ref "J3") (pin "27") (pinfunction "27_27") (pintype "bidirectional"))
      (node (ref "P10") (pin "2") (pinfunction "2_2") (pintype "passive"))
    )
    (net (code "194") (name "/TRTDIN_P13") (class "Default")
      (node (ref "J3") (pin "29") (pinfunction "29_29") (pintype "bidirectional"))
      (node (ref "P12") (pin "2") (pinfunction "2_2") (pintype "passive"))
    )
    (net (code "195") (name "/TRTDIN_P14") (class "Default")
      (node (ref "J3") (pin "31") (pinfunction "31_31") (pintype "bidirectional"))
      (node (ref "P14") (pin "2") (pinfunction "2_2") (pintype "passive"))
    )
    (net (code "196") (name "/TRTDIN_P15") (class "Default")
      (node (ref "J3") (pin "33") (pinfunction "33_33") (pintype "bidirectional"))
      (node (ref "P16") (pin "2") (pinfunction "2_2") (pintype "passive"))
    )
    (net (code "197") (name "GND1") (class "Default")
      (node (ref "C1") (pin "1") (pinfunction "1_1") (pintype "passive"))
      (node (ref "C4") (pin "1") (pinfunction "1_1") (pintype "passive"))
      (node (ref "D2") (pin "2") (pinfunction "GND_2") (pintype "power_in"))
      (node (ref "IC2") (pin "2") (pinfunction "VSS_2") (pintype "power_in"))
      (node (ref "J3") (pin "1") (pinfunction "1_1") (pintype "bidirectional"))
      (node (ref "LD2") (pin "1") (pinfunction "C_1") (pintype "passive"))
      (node (ref "R2") (pin "2") (pinfunction "2_2") (pintype "passive"))
      (node (ref "TP7") (pin "1") (pinfunction "1_1") (pintype "bidirectional"))
    )
    (net (code "198") (name "GND2") (class "Default")
      (node (ref "C2") (pin "1") (pinfunction "1_1") (pintype "passive"))
      (node (ref "C3") (pin "1") (pinfunction "1_1") (pintype "passive"))
      (node (ref "D1") (pin "2") (pinfunction "GND_2") (pintype "power_in"))
      (node (ref "IC1") (pin "2") (pinfunction "VSS_2") (pintype "power_in"))
      (node (ref "J1") (pin "1") (pinfunction "1_1") (pintype "bidirectional"))
      (node (ref "J1") (pin "10") (pinfunction "10_10") (pintype "bidirectional"))
      (node (ref "J10") (pin "1") (pinfunction "1_1") (pintype "bidirectional"))
      (node (ref "J10") (pin "10") (pinfunction "10_10") (pintype "bidirectional"))
      (node (ref "J2") (pin "1") (pinfunction "1_1") (pintype "bidirectional"))
      (node (ref "J2") (pin "10") (pinfunction "10_10") (pintype "bidirectional"))
      (node (ref "J4") (pin "1") (pinfunction "1_1") (pintype "bidirectional"))
      (node (ref "J5") (pin "1") (pinfunction "1_1") (pintype "bidirectional"))
      (node (ref "J5") (pin "10") (pinfunction "10_10") (pintype "bidirectional"))
      (node (ref "J6") (pin "1") (pinfunction "1_1") (pintype "bidirectional"))
      (node (ref "J6") (pin "10") (pinfunction "10_10") (pintype "bidirectional"))
      (node (ref "J7") (pin "1") (pinfunction "1_1") (pintype "bidirectional"))
      (node (ref "J7") (pin "10") (pinfunction "10_10") (pintype "bidirectional"))
      (node (ref "J8") (pin "1") (pinfunction "1_1") (pintype "bidirectional"))
      (node (ref "J8") (pin "10") (pinfunction "10_10") (pintype "bidirectional"))
      (node (ref "J9") (pin "1") (pinfunction "1_1") (pintype "bidirectional"))
      (node (ref "J9") (pin "10") (pinfunction "10_10") (pintype "bidirectional"))
      (node (ref "LD1") (pin "1") (pinfunction "C_1") (pintype "passive"))
      (node (ref "R3") (pin "2") (pinfunction "2_2") (pintype "passive"))
      (node (ref "TP4") (pin "1") (pinfunction "1_1") (pintype "bidirectional"))
    )
    (net (code "199") (name "GND3") (class "Default")
      (node (ref "J11") (pin "1") (pinfunction "1_1") (pintype "bidirectional"))
      (node (ref "J11") (pin "10") (pinfunction "10_10") (pintype "bidirectional"))
    )
    (net (code "200") (name "GND4") (class "Default")
      (node (ref "J12") (pin "1") (pinfunction "1_1") (pintype "bidirectional"))
      (node (ref "J12") (pin "10") (pinfunction "10_10") (pintype "bidirectional"))
    )
    (net (code "201") (name "GND5") (class "Default")
      (node (ref "J29") (pin "1") (pinfunction "1_1") (pintype "bidirectional"))
      (node (ref "J29") (pin "10") (pinfunction "10_10") (pintype "bidirectional"))
    )
    (net (code "202") (name "GND6") (class "Default")
      (node (ref "J30") (pin "1") (pinfunction "1_1") (pintype "bidirectional"))
      (node (ref "J30") (pin "10") (pinfunction "10_10") (pintype "bidirectional"))
    )
    (net (code "203") (name "GND7") (class "Default")
      (node (ref "J47") (pin "1") (pinfunction "1_1") (pintype "bidirectional"))
      (node (ref "J47") (pin "10") (pinfunction "10_10") (pintype "bidirectional"))
    )
    (net (code "204") (name "GND8") (class "Default")
      (node (ref "J48") (pin "1") (pinfunction "1_1") (pintype "bidirectional"))
      (node (ref "J48") (pin "10") (pinfunction "10_10") (pintype "bidirectional"))
    )
    (net (code "205") (name "GND9") (class "Default")
      (node (ref "J65") (pin "1") (pinfunction "1_1") (pintype "bidirectional"))
      (node (ref "J65") (pin "10") (pinfunction "10_10") (pintype "bidirectional"))
    )
    (net (code "206") (name "GND10") (class "Default")
      (node (ref "J66") (pin "1") (pinfunction "1_1") (pintype "bidirectional"))
      (node (ref "J66") (pin "10") (pinfunction "10_10") (pintype "bidirectional"))
    )
    (net (code "207") (name "Net-(C1-Pad2)") (class "Default")
      (node (ref "C1") (pin "2") (pinfunction "2_2") (pintype "passive"))
      (node (ref "J3") (pin "70") (pinfunction "70_70") (pintype "passive"))
    )
    (net (code "208") (name "Net-(C2-Pad2)") (class "Default")
      (node (ref "C2") (pin "2") (pinfunction "2_2") (pintype "passive"))
      (node (ref "J4") (pin "70") (pinfunction "70_70") (pintype "passive"))
    )
    (net (code "209") (name "Net-(J3-Pad69)") (class "Default")
      (node (ref "J3") (pin "69") (pinfunction "69_69") (pintype "passive"))
      (node (ref "R2") (pin "1") (pinfunction "1_1") (pintype "passive"))
    )
    (net (code "210") (name "Net-(J4-Pad69)") (class "Default")
      (node (ref "J4") (pin "69") (pinfunction "69_69") (pintype "passive"))
      (node (ref "R3") (pin "1") (pinfunction "1_1") (pintype "passive"))
    )
    (net (code "211") (name "Net-(LD1-A)") (class "Default")
      (node (ref "LD1") (pin "2") (pinfunction "A_2") (pintype "passive"))
      (node (ref "R1") (pin "1") (pinfunction "1_1") (pintype "passive"))
    )
    (net (code "212") (name "Net-(LD2-A)") (class "Default")
      (node (ref "LD2") (pin "2") (pinfunction "A_2") (pintype "passive"))
      (node (ref "R4") (pin "1") (pinfunction "1_1") (pintype "passive"))
    )
    (net (code "213") (name "P3V3_EXP1") (class "Default")
      (node (ref "C4") (pin "2") (pinfunction "2_2") (pintype "passive"))
      (node (ref "D2") (pin "5") (pinfunction "VBUS_5") (pintype "power_in"))
      (node (ref "IC2") (pin "4") (pinfunction "VCC_4") (pintype "power_in"))
      (node (ref "J3") (pin "35") (pinfunction "35_35") (pintype "bidirectional"))
      (node (ref "R4") (pin "2") (pinfunction "2_2") (pintype "passive"))
      (node (ref "TP8") (pin "1") (pinfunction "1_1") (pintype "bidirectional"))
    )
    (net (code "214") (name "P3V3_EXP2") (class "Default")
      (node (ref "C3") (pin "2") (pinfunction "2_2") (pintype "passive"))
      (node (ref "D1") (pin "5") (pinfunction "VBUS_5") (pintype "power_in"))
      (node (ref "IC1") (pin "4") (pinfunction "VCC_4") (pintype "power_in"))
      (node (ref "J4") (pin "35") (pinfunction "35_35") (pintype "bidirectional"))
      (node (ref "R1") (pin "2") (pinfunction "2_2") (pintype "passive"))
      (node (ref "TP3") (pin "1") (pinfunction "1_1") (pintype "bidirectional"))
    )
    (net (code "215") (name "unconnected-(D1-I{slash}O1-Pad1)") (class "Default")
      (node (ref "D1") (pin "1") (pinfunction "I/O1_1") (pintype "bidirectional+no_connect"))
    )
    (net (code "216") (name "unconnected-(D1-I{slash}O4-Pad6)") (class "Default")
      (node (ref "D1") (pin "6") (pinfunction "I/O4_6") (pintype "bidirectional+no_connect"))
    )
    (net (code "217") (name "unconnected-(D2-I{slash}O1-Pad1)") (class "Default")
      (node (ref "D2") (pin "1") (pinfunction "I/O1_1") (pintype "bidirectional+no_connect"))
    )
    (net (code "218") (name "unconnected-(D2-I{slash}O4-Pad6)") (class "Default")
      (node (ref "D2") (pin "6") (pinfunction "I/O4_6") (pintype "bidirectional+no_connect"))
    )
    (net (code "219") (name "unconnected-(IC1-NC-Pad5)") (class "Default")
      (node (ref "IC1") (pin "5") (pinfunction "NC_5") (pintype "passive"))
    )
    (net (code "220") (name "unconnected-(IC2-NC-Pad5)") (class "Default")
      (node (ref "IC2") (pin "5") (pinfunction "NC_5") (pintype "passive"))
    )
  )
)
